# 03.net
KiCad netlist of a schematic drawn in Altium Designer
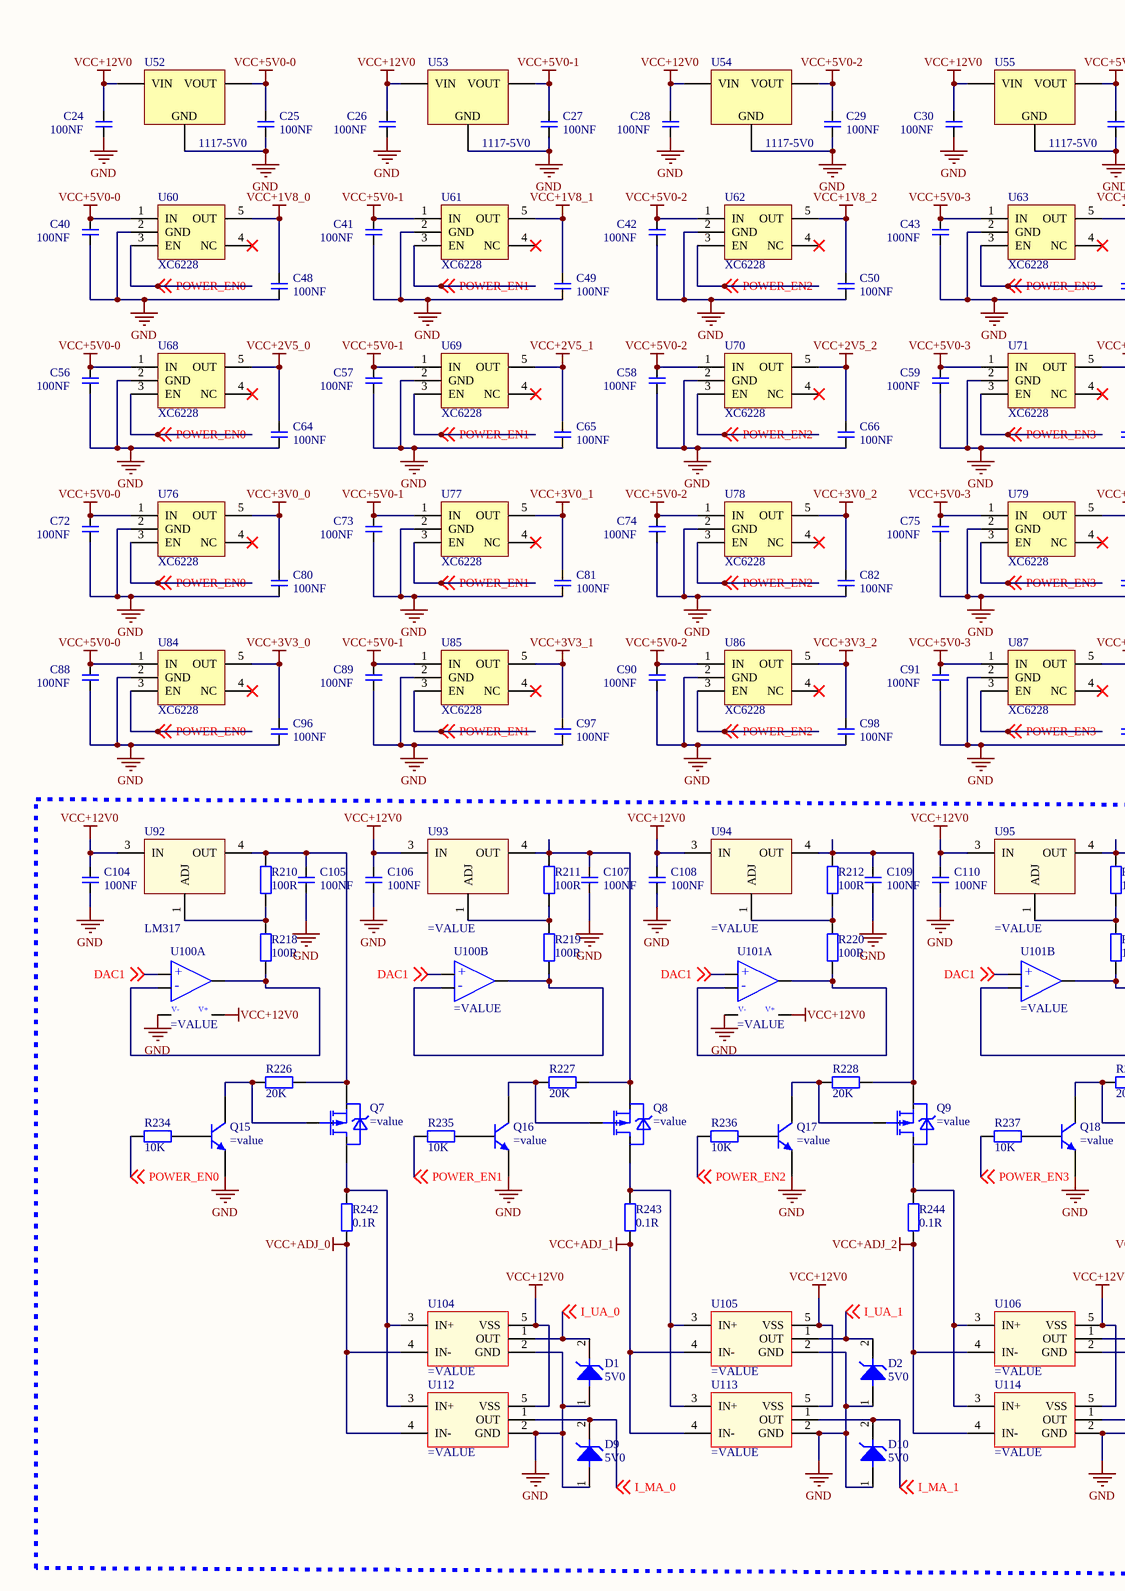
[diagram p0: 通用工装板03.SchDoc, left]
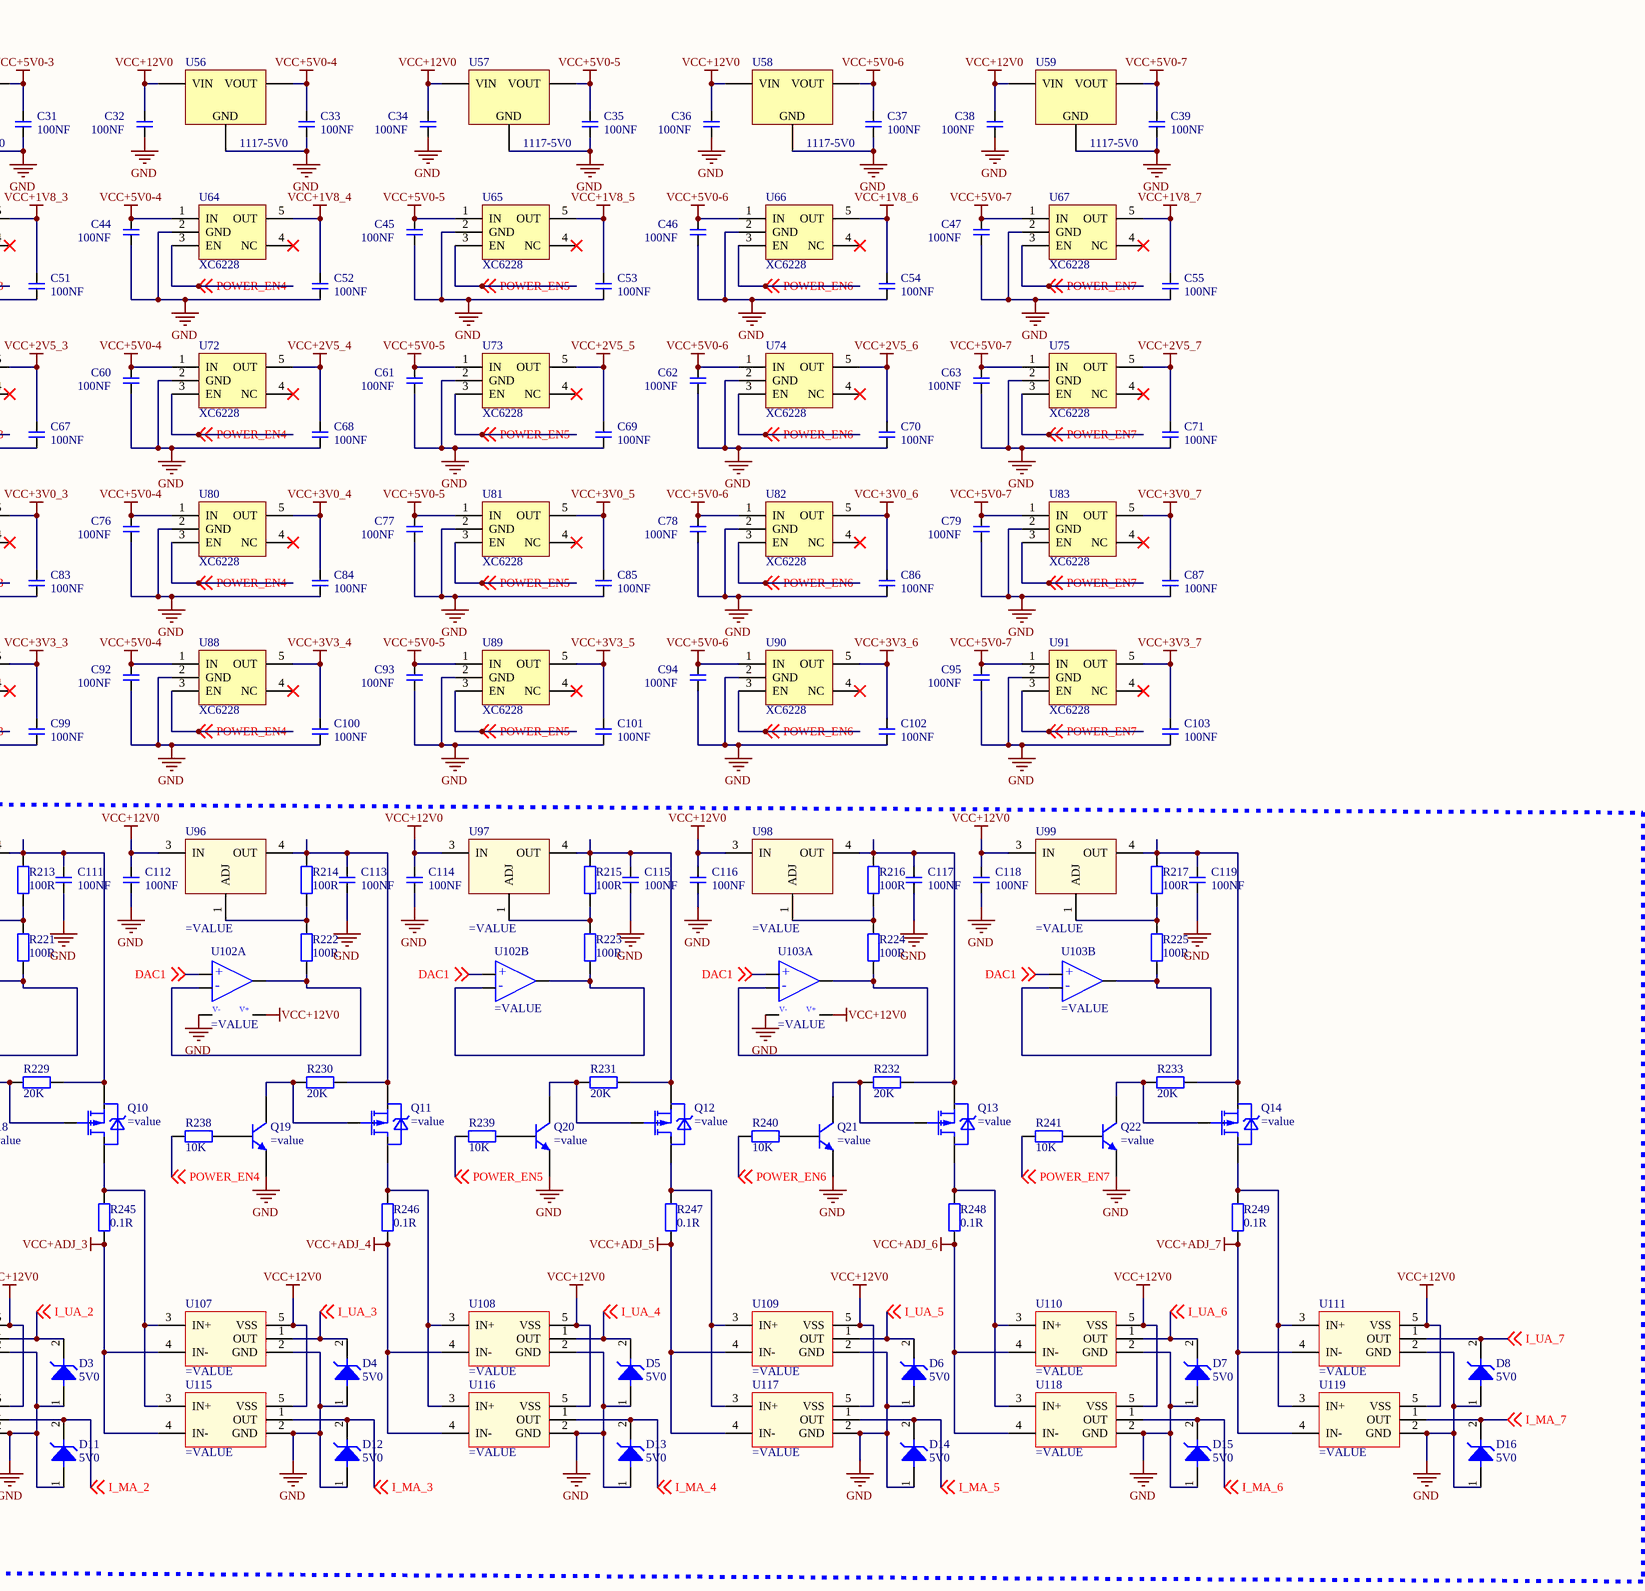
[diagram p1: 通用工装板03.SchDoc, right]

(export (version "E")
  (design (tool "Eeschema 10.0.6"))
  (components
    (comp (ref "C24")
      (value "100NF")
      (footprint "c0402")
      (description "无极性电容")
      (libsource (lib "瑞臻信息") (part "无极性电容"))
    )
    (comp (ref "C25")
      (value "100NF")
      (footprint "c0402")
      (description "无极性电容")
      (libsource (lib "瑞臻信息") (part "无极性电容"))
    )
    (comp (ref "C26")
      (value "100NF")
      (footprint "c0402")
      (description "无极性电容")
      (libsource (lib "瑞臻信息") (part "无极性电容"))
    )
    (comp (ref "C27")
      (value "100NF")
      (footprint "c0402")
      (description "无极性电容")
      (libsource (lib "瑞臻信息") (part "无极性电容"))
    )
    (comp (ref "C28")
      (value "100NF")
      (footprint "c0402")
      (description "无极性电容")
      (libsource (lib "瑞臻信息") (part "无极性电容"))
    )
    (comp (ref "C29")
      (value "100NF")
      (footprint "c0402")
      (description "无极性电容")
      (libsource (lib "瑞臻信息") (part "无极性电容"))
    )
    (comp (ref "C30")
      (value "100NF")
      (footprint "c0402")
      (description "无极性电容")
      (libsource (lib "瑞臻信息") (part "无极性电容"))
    )
    (comp (ref "C31")
      (value "100NF")
      (footprint "c0402")
      (description "无极性电容")
      (libsource (lib "瑞臻信息") (part "无极性电容"))
    )
    (comp (ref "C32")
      (value "100NF")
      (footprint "c0402")
      (description "无极性电容")
      (libsource (lib "瑞臻信息") (part "无极性电容"))
    )
    (comp (ref "C33")
      (value "100NF")
      (footprint "c0402")
      (description "无极性电容")
      (libsource (lib "瑞臻信息") (part "无极性电容"))
    )
    (comp (ref "C34")
      (value "100NF")
      (footprint "c0402")
      (description "无极性电容")
      (libsource (lib "瑞臻信息") (part "无极性电容"))
    )
    (comp (ref "C35")
      (value "100NF")
      (footprint "c0402")
      (description "无极性电容")
      (libsource (lib "瑞臻信息") (part "无极性电容"))
    )
    (comp (ref "C36")
      (value "100NF")
      (footprint "c0402")
      (description "无极性电容")
      (libsource (lib "瑞臻信息") (part "无极性电容"))
    )
    (comp (ref "C37")
      (value "100NF")
      (footprint "c0402")
      (description "无极性电容")
      (libsource (lib "瑞臻信息") (part "无极性电容"))
    )
    (comp (ref "C38")
      (value "100NF")
      (footprint "c0402")
      (description "无极性电容")
      (libsource (lib "瑞臻信息") (part "无极性电容"))
    )
    (comp (ref "C39")
      (value "100NF")
      (footprint "c0402")
      (description "无极性电容")
      (libsource (lib "瑞臻信息") (part "无极性电容"))
    )
    (comp (ref "C40")
      (value "100NF")
      (footprint "c0402")
      (description "无极性电容")
      (libsource (lib "瑞臻信息") (part "无极性电容"))
    )
    (comp (ref "C41")
      (value "100NF")
      (footprint "c0402")
      (description "无极性电容")
      (libsource (lib "瑞臻信息") (part "无极性电容"))
    )
    (comp (ref "C42")
      (value "100NF")
      (footprint "c0402")
      (description "无极性电容")
      (libsource (lib "瑞臻信息") (part "无极性电容"))
    )
    (comp (ref "C43")
      (value "100NF")
      (footprint "c0402")
      (description "无极性电容")
      (libsource (lib "瑞臻信息") (part "无极性电容"))
    )
    (comp (ref "C44")
      (value "100NF")
      (footprint "c0402")
      (description "无极性电容")
      (libsource (lib "瑞臻信息") (part "无极性电容"))
    )
    (comp (ref "C45")
      (value "100NF")
      (footprint "c0402")
      (description "无极性电容")
      (libsource (lib "瑞臻信息") (part "无极性电容"))
    )
    (comp (ref "C46")
      (value "100NF")
      (footprint "c0402")
      (description "无极性电容")
      (libsource (lib "瑞臻信息") (part "无极性电容"))
    )
    (comp (ref "C47")
      (value "100NF")
      (footprint "c0402")
      (description "无极性电容")
      (libsource (lib "瑞臻信息") (part "无极性电容"))
    )
    (comp (ref "C48")
      (value "100NF")
      (footprint "c0402")
      (description "无极性电容")
      (libsource (lib "瑞臻信息") (part "无极性电容"))
    )
    (comp (ref "C49")
      (value "100NF")
      (footprint "c0402")
      (description "无极性电容")
      (libsource (lib "瑞臻信息") (part "无极性电容"))
    )
    (comp (ref "C50")
      (value "100NF")
      (footprint "c0402")
      (description "无极性电容")
      (libsource (lib "瑞臻信息") (part "无极性电容"))
    )
    (comp (ref "C51")
      (value "100NF")
      (footprint "c0402")
      (description "无极性电容")
      (libsource (lib "瑞臻信息") (part "无极性电容"))
    )
    (comp (ref "C52")
      (value "100NF")
      (footprint "c0402")
      (description "无极性电容")
      (libsource (lib "瑞臻信息") (part "无极性电容"))
    )
    (comp (ref "C53")
      (value "100NF")
      (footprint "c0402")
      (description "无极性电容")
      (libsource (lib "瑞臻信息") (part "无极性电容"))
    )
    (comp (ref "C54")
      (value "100NF")
      (footprint "c0402")
      (description "无极性电容")
      (libsource (lib "瑞臻信息") (part "无极性电容"))
    )
    (comp (ref "C55")
      (value "100NF")
      (footprint "c0402")
      (description "无极性电容")
      (libsource (lib "瑞臻信息") (part "无极性电容"))
    )
    (comp (ref "C56")
      (value "100NF")
      (footprint "c0402")
      (description "无极性电容")
      (libsource (lib "瑞臻信息") (part "无极性电容"))
    )
    (comp (ref "C57")
      (value "100NF")
      (footprint "c0402")
      (description "无极性电容")
      (libsource (lib "瑞臻信息") (part "无极性电容"))
    )
    (comp (ref "C58")
      (value "100NF")
      (footprint "c0402")
      (description "无极性电容")
      (libsource (lib "瑞臻信息") (part "无极性电容"))
    )
    (comp (ref "C59")
      (value "100NF")
      (footprint "c0402")
      (description "无极性电容")
      (libsource (lib "瑞臻信息") (part "无极性电容"))
    )
    (comp (ref "C60")
      (value "100NF")
      (footprint "c0402")
      (description "无极性电容")
      (libsource (lib "瑞臻信息") (part "无极性电容"))
    )
    (comp (ref "C61")
      (value "100NF")
      (footprint "c0402")
      (description "无极性电容")
      (libsource (lib "瑞臻信息") (part "无极性电容"))
    )
    (comp (ref "C62")
      (value "100NF")
      (footprint "c0402")
      (description "无极性电容")
      (libsource (lib "瑞臻信息") (part "无极性电容"))
    )
    (comp (ref "C63")
      (value "100NF")
      (footprint "c0402")
      (description "无极性电容")
      (libsource (lib "瑞臻信息") (part "无极性电容"))
    )
    (comp (ref "C64")
      (value "100NF")
      (footprint "c0402")
      (description "无极性电容")
      (libsource (lib "瑞臻信息") (part "无极性电容"))
    )
    (comp (ref "C65")
      (value "100NF")
      (footprint "c0402")
      (description "无极性电容")
      (libsource (lib "瑞臻信息") (part "无极性电容"))
    )
    (comp (ref "C66")
      (value "100NF")
      (footprint "c0402")
      (description "无极性电容")
      (libsource (lib "瑞臻信息") (part "无极性电容"))
    )
    (comp (ref "C67")
      (value "100NF")
      (footprint "c0402")
      (description "无极性电容")
      (libsource (lib "瑞臻信息") (part "无极性电容"))
    )
    (comp (ref "C68")
      (value "100NF")
      (footprint "c0402")
      (description "无极性电容")
      (libsource (lib "瑞臻信息") (part "无极性电容"))
    )
    (comp (ref "C69")
      (value "100NF")
      (footprint "c0402")
      (description "无极性电容")
      (libsource (lib "瑞臻信息") (part "无极性电容"))
    )
    (comp (ref "C70")
      (value "100NF")
      (footprint "c0402")
      (description "无极性电容")
      (libsource (lib "瑞臻信息") (part "无极性电容"))
    )
    (comp (ref "C71")
      (value "100NF")
      (footprint "c0402")
      (description "无极性电容")
      (libsource (lib "瑞臻信息") (part "无极性电容"))
    )
    (comp (ref "C72")
      (value "100NF")
      (footprint "c0402")
      (description "无极性电容")
      (libsource (lib "瑞臻信息") (part "无极性电容"))
    )
    (comp (ref "C73")
      (value "100NF")
      (footprint "c0402")
      (description "无极性电容")
      (libsource (lib "瑞臻信息") (part "无极性电容"))
    )
    (comp (ref "C74")
      (value "100NF")
      (footprint "c0402")
      (description "无极性电容")
      (libsource (lib "瑞臻信息") (part "无极性电容"))
    )
    (comp (ref "C75")
      (value "100NF")
      (footprint "c0402")
      (description "无极性电容")
      (libsource (lib "瑞臻信息") (part "无极性电容"))
    )
    (comp (ref "C76")
      (value "100NF")
      (footprint "c0402")
      (description "无极性电容")
      (libsource (lib "瑞臻信息") (part "无极性电容"))
    )
    (comp (ref "C77")
      (value "100NF")
      (footprint "c0402")
      (description "无极性电容")
      (libsource (lib "瑞臻信息") (part "无极性电容"))
    )
    (comp (ref "C78")
      (value "100NF")
      (footprint "c0402")
      (description "无极性电容")
      (libsource (lib "瑞臻信息") (part "无极性电容"))
    )
    (comp (ref "C79")
      (value "100NF")
      (footprint "c0402")
      (description "无极性电容")
      (libsource (lib "瑞臻信息") (part "无极性电容"))
    )
    (comp (ref "C80")
      (value "100NF")
      (footprint "c0402")
      (description "无极性电容")
      (libsource (lib "瑞臻信息") (part "无极性电容"))
    )
    (comp (ref "C81")
      (value "100NF")
      (footprint "c0402")
      (description "无极性电容")
      (libsource (lib "瑞臻信息") (part "无极性电容"))
    )
    (comp (ref "C82")
      (value "100NF")
      (footprint "c0402")
      (description "无极性电容")
      (libsource (lib "瑞臻信息") (part "无极性电容"))
    )
    (comp (ref "C83")
      (value "100NF")
      (footprint "c0402")
      (description "无极性电容")
      (libsource (lib "瑞臻信息") (part "无极性电容"))
    )
    (comp (ref "C84")
      (value "100NF")
      (footprint "c0402")
      (description "无极性电容")
      (libsource (lib "瑞臻信息") (part "无极性电容"))
    )
    (comp (ref "C85")
      (value "100NF")
      (footprint "c0402")
      (description "无极性电容")
      (libsource (lib "瑞臻信息") (part "无极性电容"))
    )
    (comp (ref "C86")
      (value "100NF")
      (footprint "c0402")
      (description "无极性电容")
      (libsource (lib "瑞臻信息") (part "无极性电容"))
    )
    (comp (ref "C87")
      (value "100NF")
      (footprint "c0402")
      (description "无极性电容")
      (libsource (lib "瑞臻信息") (part "无极性电容"))
    )
    (comp (ref "C88")
      (value "100NF")
      (footprint "c0402")
      (description "无极性电容")
      (libsource (lib "瑞臻信息") (part "无极性电容"))
    )
    (comp (ref "C89")
      (value "100NF")
      (footprint "c0402")
      (description "无极性电容")
      (libsource (lib "瑞臻信息") (part "无极性电容"))
    )
    (comp (ref "C90")
      (value "100NF")
      (footprint "c0402")
      (description "无极性电容")
      (libsource (lib "瑞臻信息") (part "无极性电容"))
    )
    (comp (ref "C91")
      (value "100NF")
      (footprint "c0402")
      (description "无极性电容")
      (libsource (lib "瑞臻信息") (part "无极性电容"))
    )
    (comp (ref "C92")
      (value "100NF")
      (footprint "c0402")
      (description "无极性电容")
      (libsource (lib "瑞臻信息") (part "无极性电容"))
    )
    (comp (ref "C93")
      (value "100NF")
      (footprint "c0402")
      (description "无极性电容")
      (libsource (lib "瑞臻信息") (part "无极性电容"))
    )
    (comp (ref "C94")
      (value "100NF")
      (footprint "c0402")
      (description "无极性电容")
      (libsource (lib "瑞臻信息") (part "无极性电容"))
    )
    (comp (ref "C95")
      (value "100NF")
      (footprint "c0402")
      (description "无极性电容")
      (libsource (lib "瑞臻信息") (part "无极性电容"))
    )
    (comp (ref "C96")
      (value "100NF")
      (footprint "c0402")
      (description "无极性电容")
      (libsource (lib "瑞臻信息") (part "无极性电容"))
    )
    (comp (ref "C97")
      (value "100NF")
      (footprint "c0402")
      (description "无极性电容")
      (libsource (lib "瑞臻信息") (part "无极性电容"))
    )
    (comp (ref "C98")
      (value "100NF")
      (footprint "c0402")
      (description "无极性电容")
      (libsource (lib "瑞臻信息") (part "无极性电容"))
    )
    (comp (ref "C99")
      (value "100NF")
      (footprint "c0402")
      (description "无极性电容")
      (libsource (lib "瑞臻信息") (part "无极性电容"))
    )
    (comp (ref "C100")
      (value "100NF")
      (footprint "c0402")
      (description "无极性电容")
      (libsource (lib "瑞臻信息") (part "无极性电容"))
    )
    (comp (ref "C101")
      (value "100NF")
      (footprint "c0402")
      (description "无极性电容")
      (libsource (lib "瑞臻信息") (part "无极性电容"))
    )
    (comp (ref "C102")
      (value "100NF")
      (footprint "c0402")
      (description "无极性电容")
      (libsource (lib "瑞臻信息") (part "无极性电容"))
    )
    (comp (ref "C103")
      (value "100NF")
      (footprint "c0402")
      (description "无极性电容")
      (libsource (lib "瑞臻信息") (part "无极性电容"))
    )
    (comp (ref "C104")
      (value "100NF")
      (footprint "c0402")
      (description "无极性电容")
      (libsource (lib "瑞臻信息") (part "无极性电容"))
    )
    (comp (ref "C105")
      (value "100NF")
      (footprint "c0402")
      (description "无极性电容")
      (libsource (lib "瑞臻信息") (part "无极性电容"))
    )
    (comp (ref "C106")
      (value "100NF")
      (footprint "c0402")
      (description "无极性电容")
      (libsource (lib "瑞臻信息") (part "无极性电容"))
    )
    (comp (ref "C107")
      (value "100NF")
      (footprint "c0402")
      (description "无极性电容")
      (libsource (lib "瑞臻信息") (part "无极性电容"))
    )
    (comp (ref "C108")
      (value "100NF")
      (footprint "c0402")
      (description "无极性电容")
      (libsource (lib "瑞臻信息") (part "无极性电容"))
    )
    (comp (ref "C109")
      (value "100NF")
      (footprint "c0402")
      (description "无极性电容")
      (libsource (lib "瑞臻信息") (part "无极性电容"))
    )
    (comp (ref "C110")
      (value "100NF")
      (footprint "c0402")
      (description "无极性电容")
      (libsource (lib "瑞臻信息") (part "无极性电容"))
    )
    (comp (ref "C111")
      (value "100NF")
      (footprint "c0402")
      (description "无极性电容")
      (libsource (lib "瑞臻信息") (part "无极性电容"))
    )
    (comp (ref "C112")
      (value "100NF")
      (footprint "c0402")
      (description "无极性电容")
      (libsource (lib "瑞臻信息") (part "无极性电容"))
    )
    (comp (ref "C113")
      (value "100NF")
      (footprint "c0402")
      (description "无极性电容")
      (libsource (lib "瑞臻信息") (part "无极性电容"))
    )
    (comp (ref "C114")
      (value "100NF")
      (footprint "c0402")
      (description "无极性电容")
      (libsource (lib "瑞臻信息") (part "无极性电容"))
    )
    (comp (ref "C115")
      (value "100NF")
      (footprint "c0402")
      (description "无极性电容")
      (libsource (lib "瑞臻信息") (part "无极性电容"))
    )
    (comp (ref "C116")
      (value "100NF")
      (footprint "c0402")
      (description "无极性电容")
      (libsource (lib "瑞臻信息") (part "无极性电容"))
    )
    (comp (ref "C117")
      (value "100NF")
      (footprint "c0402")
      (description "无极性电容")
      (libsource (lib "瑞臻信息") (part "无极性电容"))
    )
    (comp (ref "C118")
      (value "100NF")
      (footprint "c0402")
      (description "无极性电容")
      (libsource (lib "瑞臻信息") (part "无极性电容"))
    )
    (comp (ref "C119")
      (value "100NF")
      (footprint "c0402")
      (description "无极性电容")
      (libsource (lib "瑞臻信息") (part "无极性电容"))
    )
    (comp (ref "D1")
      (value "5V0")
      (footprint "LL34_2P_D1R5H3R7")
      (description "齐纳二极管")
      (libsource (lib "瑞臻信息") (part "齐纳二极管"))
    )
    (comp (ref "D2")
      (value "5V0")
      (footprint "LL34_2P_D1R5H3R7")
      (description "齐纳二极管")
      (libsource (lib "瑞臻信息") (part "齐纳二极管"))
    )
    (comp (ref "D3")
      (value "5V0")
      (footprint "LL34_2P_D1R5H3R7")
      (description "齐纳二极管")
      (libsource (lib "瑞臻信息") (part "齐纳二极管"))
    )
    (comp (ref "D4")
      (value "5V0")
      (footprint "LL34_2P_D1R5H3R7")
      (description "齐纳二极管")
      (libsource (lib "瑞臻信息") (part "齐纳二极管"))
    )
    (comp (ref "D5")
      (value "5V0")
      (footprint "LL34_2P_D1R5H3R7")
      (description "齐纳二极管")
      (libsource (lib "瑞臻信息") (part "齐纳二极管"))
    )
    (comp (ref "D6")
      (value "5V0")
      (footprint "LL34_2P_D1R5H3R7")
      (description "齐纳二极管")
      (libsource (lib "瑞臻信息") (part "齐纳二极管"))
    )
    (comp (ref "D7")
      (value "5V0")
      (footprint "LL34_2P_D1R5H3R7")
      (description "齐纳二极管")
      (libsource (lib "瑞臻信息") (part "齐纳二极管"))
    )
    (comp (ref "D8")
      (value "5V0")
      (footprint "LL34_2P_D1R5H3R7")
      (description "齐纳二极管")
      (libsource (lib "瑞臻信息") (part "齐纳二极管"))
    )
    (comp (ref "D9")
      (value "5V0")
      (footprint "LL34_2P_D1R5H3R7")
      (description "齐纳二极管")
      (libsource (lib "瑞臻信息") (part "齐纳二极管"))
    )
    (comp (ref "D10")
      (value "5V0")
      (footprint "LL34_2P_D1R5H3R7")
      (description "齐纳二极管")
      (libsource (lib "瑞臻信息") (part "齐纳二极管"))
    )
    (comp (ref "D11")
      (value "5V0")
      (footprint "LL34_2P_D1R5H3R7")
      (description "齐纳二极管")
      (libsource (lib "瑞臻信息") (part "齐纳二极管"))
    )
    (comp (ref "D12")
      (value "5V0")
      (footprint "LL34_2P_D1R5H3R7")
      (description "齐纳二极管")
      (libsource (lib "瑞臻信息") (part "齐纳二极管"))
    )
    (comp (ref "D13")
      (value "5V0")
      (footprint "LL34_2P_D1R5H3R7")
      (description "齐纳二极管")
      (libsource (lib "瑞臻信息") (part "齐纳二极管"))
    )
    (comp (ref "D14")
      (value "5V0")
      (footprint "LL34_2P_D1R5H3R7")
      (description "齐纳二极管")
      (libsource (lib "瑞臻信息") (part "齐纳二极管"))
    )
    (comp (ref "D15")
      (value "5V0")
      (footprint "LL34_2P_D1R5H3R7")
      (description "齐纳二极管")
      (libsource (lib "瑞臻信息") (part "齐纳二极管"))
    )
    (comp (ref "D16")
      (value "5V0")
      (footprint "LL34_2P_D1R5H3R7")
      (description "齐纳二极管")
      (libsource (lib "瑞臻信息") (part "齐纳二极管"))
    )
    (comp (ref "Q7")
      (value "~")
      (footprint "SOT23_3P_0R95_1R3X2R9")
      (description "P-MOS")
      (libsource (lib "瑞臻信息") (part "P-MOS"))
    )
    (comp (ref "Q8")
      (value "~")
      (footprint "SOT23_3P_0R95_1R3X2R9")
      (description "P-MOS")
      (libsource (lib "瑞臻信息") (part "P-MOS"))
    )
    (comp (ref "Q9")
      (value "~")
      (footprint "SOT23_3P_0R95_1R3X2R9")
      (description "P-MOS")
      (libsource (lib "瑞臻信息") (part "P-MOS"))
    )
    (comp (ref "Q10")
      (value "~")
      (footprint "SOT23_3P_0R95_1R3X2R9")
      (description "P-MOS")
      (libsource (lib "瑞臻信息") (part "P-MOS"))
    )
    (comp (ref "Q11")
      (value "~")
      (footprint "SOT23_3P_0R95_1R3X2R9")
      (description "P-MOS")
      (libsource (lib "瑞臻信息") (part "P-MOS"))
    )
    (comp (ref "Q12")
      (value "~")
      (footprint "SOT23_3P_0R95_1R3X2R9")
      (description "P-MOS")
      (libsource (lib "瑞臻信息") (part "P-MOS"))
    )
    (comp (ref "Q13")
      (value "~")
      (footprint "SOT23_3P_0R95_1R3X2R9")
      (description "P-MOS")
      (libsource (lib "瑞臻信息") (part "P-MOS"))
    )
    (comp (ref "Q14")
      (value "~")
      (footprint "SOT23_3P_0R95_1R3X2R9")
      (description "P-MOS")
      (libsource (lib "瑞臻信息") (part "P-MOS"))
    )
    (comp (ref "Q15")
      (value "~")
      (footprint "SOT23_3P_0R95_1R3X2R9")
      (description "NPN三极管")
      (libsource (lib "瑞臻信息") (part "NPN三极管"))
    )
    (comp (ref "Q16")
      (value "~")
      (footprint "SOT23_3P_0R95_1R3X2R9")
      (description "NPN三极管")
      (libsource (lib "瑞臻信息") (part "NPN三极管"))
    )
    (comp (ref "Q17")
      (value "~")
      (footprint "SOT23_3P_0R95_1R3X2R9")
      (description "NPN三极管")
      (libsource (lib "瑞臻信息") (part "NPN三极管"))
    )
    (comp (ref "Q18")
      (value "~")
      (footprint "SOT23_3P_0R95_1R3X2R9")
      (description "NPN三极管")
      (libsource (lib "瑞臻信息") (part "NPN三极管"))
    )
    (comp (ref "Q19")
      (value "~")
      (footprint "SOT23_3P_0R95_1R3X2R9")
      (description "NPN三极管")
      (libsource (lib "瑞臻信息") (part "NPN三极管"))
    )
    (comp (ref "Q20")
      (value "~")
      (footprint "SOT23_3P_0R95_1R3X2R9")
      (description "NPN三极管")
      (libsource (lib "瑞臻信息") (part "NPN三极管"))
    )
    (comp (ref "Q21")
      (value "~")
      (footprint "SOT23_3P_0R95_1R3X2R9")
      (description "NPN三极管")
      (libsource (lib "瑞臻信息") (part "NPN三极管"))
    )
    (comp (ref "Q22")
      (value "~")
      (footprint "SOT23_3P_0R95_1R3X2R9")
      (description "NPN三极管")
      (libsource (lib "瑞臻信息") (part "NPN三极管"))
    )
    (comp (ref "R210")
      (value "100R")
      (footprint "r0402")
      (description "普通电阻")
      (libsource (lib "") (part "普通电阻_1"))
    )
    (comp (ref "R211")
      (value "100R")
      (footprint "r0402")
      (description "普通电阻")
      (libsource (lib "") (part "普通电阻_1"))
    )
    (comp (ref "R212")
      (value "100R")
      (footprint "r0402")
      (description "普通电阻")
      (libsource (lib "") (part "普通电阻_1"))
    )
    (comp (ref "R213")
      (value "100R")
      (footprint "r0402")
      (description "普通电阻")
      (libsource (lib "") (part "普通电阻_1"))
    )
    (comp (ref "R214")
      (value "100R")
      (footprint "r0402")
      (description "普通电阻")
      (libsource (lib "") (part "普通电阻_1"))
    )
    (comp (ref "R215")
      (value "100R")
      (footprint "r0402")
      (description "普通电阻")
      (libsource (lib "") (part "普通电阻_1"))
    )
    (comp (ref "R216")
      (value "100R")
      (footprint "r0402")
      (description "普通电阻")
      (libsource (lib "") (part "普通电阻_1"))
    )
    (comp (ref "R217")
      (value "100R")
      (footprint "r0402")
      (description "普通电阻")
      (libsource (lib "") (part "普通电阻_1"))
    )
    (comp (ref "R218")
      (value "100R")
      (footprint "r0402")
      (description "普通电阻")
      (libsource (lib "") (part "普通电阻_1"))
    )
    (comp (ref "R219")
      (value "100R")
      (footprint "r0402")
      (description "普通电阻")
      (libsource (lib "") (part "普通电阻_1"))
    )
    (comp (ref "R220")
      (value "100R")
      (footprint "r0402")
      (description "普通电阻")
      (libsource (lib "") (part "普通电阻_1"))
    )
    (comp (ref "R221")
      (value "100R")
      (footprint "r0402")
      (description "普通电阻")
      (libsource (lib "") (part "普通电阻_1"))
    )
    (comp (ref "R222")
      (value "100R")
      (footprint "r0402")
      (description "普通电阻")
      (libsource (lib "") (part "普通电阻_1"))
    )
    (comp (ref "R223")
      (value "100R")
      (footprint "r0402")
      (description "普通电阻")
      (libsource (lib "") (part "普通电阻_1"))
    )
    (comp (ref "R224")
      (value "100R")
      (footprint "r0402")
      (description "普通电阻")
      (libsource (lib "") (part "普通电阻_1"))
    )
    (comp (ref "R225")
      (value "100R")
      (footprint "r0402")
      (description "普通电阻")
      (libsource (lib "") (part "普通电阻_1"))
    )
    (comp (ref "R226")
      (value "20K")
      (footprint "r0402")
      (description "普通电阻")
      (libsource (lib "瑞臻信息") (part "普通电阻"))
    )
    (comp (ref "R227")
      (value "20K")
      (footprint "r0402")
      (description "普通电阻")
      (libsource (lib "瑞臻信息") (part "普通电阻"))
    )
    (comp (ref "R228")
      (value "20K")
      (footprint "r0402")
      (description "普通电阻")
      (libsource (lib "瑞臻信息") (part "普通电阻"))
    )
    (comp (ref "R229")
      (value "20K")
      (footprint "r0402")
      (description "普通电阻")
      (libsource (lib "瑞臻信息") (part "普通电阻"))
    )
    (comp (ref "R230")
      (value "20K")
      (footprint "r0402")
      (description "普通电阻")
      (libsource (lib "瑞臻信息") (part "普通电阻"))
    )
    (comp (ref "R231")
      (value "20K")
      (footprint "r0402")
      (description "普通电阻")
      (libsource (lib "瑞臻信息") (part "普通电阻"))
    )
    (comp (ref "R232")
      (value "20K")
      (footprint "r0402")
      (description "普通电阻")
      (libsource (lib "瑞臻信息") (part "普通电阻"))
    )
    (comp (ref "R233")
      (value "20K")
      (footprint "r0402")
      (description "普通电阻")
      (libsource (lib "瑞臻信息") (part "普通电阻"))
    )
    (comp (ref "R234")
      (value "10K")
      (footprint "r0402")
      (description "普通电阻")
      (libsource (lib "瑞臻信息") (part "普通电阻"))
    )
    (comp (ref "R235")
      (value "10K")
      (footprint "r0402")
      (description "普通电阻")
      (libsource (lib "瑞臻信息") (part "普通电阻"))
    )
    (comp (ref "R236")
      (value "10K")
      (footprint "r0402")
      (description "普通电阻")
      (libsource (lib "瑞臻信息") (part "普通电阻"))
    )
    (comp (ref "R237")
      (value "10K")
      (footprint "r0402")
      (description "普通电阻")
      (libsource (lib "瑞臻信息") (part "普通电阻"))
    )
    (comp (ref "R238")
      (value "10K")
      (footprint "r0402")
      (description "普通电阻")
      (libsource (lib "瑞臻信息") (part "普通电阻"))
    )
    (comp (ref "R239")
      (value "10K")
      (footprint "r0402")
      (description "普通电阻")
      (libsource (lib "瑞臻信息") (part "普通电阻"))
    )
    (comp (ref "R240")
      (value "10K")
      (footprint "r0402")
      (description "普通电阻")
      (libsource (lib "瑞臻信息") (part "普通电阻"))
    )
    (comp (ref "R241")
      (value "10K")
      (footprint "r0402")
      (description "普通电阻")
      (libsource (lib "瑞臻信息") (part "普通电阻"))
    )
    (comp (ref "R242")
      (value "0.1R")
      (footprint "r0603")
      (description "普通电阻")
      (libsource (lib "") (part "普通电阻_2"))
    )
    (comp (ref "R243")
      (value "0.1R")
      (footprint "r0603")
      (description "普通电阻")
      (libsource (lib "") (part "普通电阻_2"))
    )
    (comp (ref "R244")
      (value "0.1R")
      (footprint "r0603")
      (description "普通电阻")
      (libsource (lib "") (part "普通电阻_2"))
    )
    (comp (ref "R245")
      (value "0.1R")
      (footprint "r0603")
      (description "普通电阻")
      (libsource (lib "") (part "普通电阻_2"))
    )
    (comp (ref "R246")
      (value "0.1R")
      (footprint "r0603")
      (description "普通电阻")
      (libsource (lib "") (part "普通电阻_2"))
    )
    (comp (ref "R247")
      (value "0.1R")
      (footprint "r0603")
      (description "普通电阻")
      (libsource (lib "") (part "普通电阻_2"))
    )
    (comp (ref "R248")
      (value "0.1R")
      (footprint "r0603")
      (description "普通电阻")
      (libsource (lib "") (part "普通电阻_2"))
    )
    (comp (ref "R249")
      (value "0.1R")
      (footprint "r0603")
      (description "普通电阻")
      (libsource (lib "") (part "普通电阻_2"))
    )
    (comp (ref "U52")
      (value "1117-5V0")
      (footprint "SOT223_4P_2R3_3R7X6R7")
      (libsource (lib "瑞臻信息") (part "AMS1117"))
    )
    (comp (ref "U53")
      (value "1117-5V0")
      (footprint "SOT223_4P_2R3_3R7X6R7")
      (libsource (lib "瑞臻信息") (part "AMS1117"))
    )
    (comp (ref "U54")
      (value "1117-5V0")
      (footprint "SOT223_4P_2R3_3R7X6R7")
      (libsource (lib "瑞臻信息") (part "AMS1117"))
    )
    (comp (ref "U55")
      (value "1117-5V0")
      (footprint "SOT223_4P_2R3_3R7X6R7")
      (libsource (lib "瑞臻信息") (part "AMS1117"))
    )
    (comp (ref "U56")
      (value "1117-5V0")
      (footprint "SOT223_4P_2R3_3R7X6R7")
      (libsource (lib "瑞臻信息") (part "AMS1117"))
    )
    (comp (ref "U57")
      (value "1117-5V0")
      (footprint "SOT223_4P_2R3_3R7X6R7")
      (libsource (lib "瑞臻信息") (part "AMS1117"))
    )
    (comp (ref "U58")
      (value "1117-5V0")
      (footprint "SOT223_4P_2R3_3R7X6R7")
      (libsource (lib "瑞臻信息") (part "AMS1117"))
    )
    (comp (ref "U59")
      (value "1117-5V0")
      (footprint "SOT223_4P_2R3_3R7X6R7")
      (libsource (lib "瑞臻信息") (part "AMS1117"))
    )
    (comp (ref "U60")
      (value "XC6228")
      (footprint "SOT23_5P_0R95_1R6X2R9")
      (libsource (lib "瑞臻信息") (part "XC6228"))
    )
    (comp (ref "U61")
      (value "XC6228")
      (footprint "SOT23_5P_0R95_1R6X2R9")
      (libsource (lib "瑞臻信息") (part "XC6228"))
    )
    (comp (ref "U62")
      (value "XC6228")
      (footprint "SOT23_5P_0R95_1R6X2R9")
      (libsource (lib "瑞臻信息") (part "XC6228"))
    )
    (comp (ref "U63")
      (value "XC6228")
      (footprint "SOT23_5P_0R95_1R6X2R9")
      (libsource (lib "瑞臻信息") (part "XC6228"))
    )
    (comp (ref "U64")
      (value "XC6228")
      (footprint "SOT23_5P_0R95_1R6X2R9")
      (libsource (lib "瑞臻信息") (part "XC6228"))
    )
    (comp (ref "U65")
      (value "XC6228")
      (footprint "SOT23_5P_0R95_1R6X2R9")
      (libsource (lib "瑞臻信息") (part "XC6228"))
    )
    (comp (ref "U66")
      (value "XC6228")
      (footprint "SOT23_5P_0R95_1R6X2R9")
      (libsource (lib "瑞臻信息") (part "XC6228"))
    )
    (comp (ref "U67")
      (value "XC6228")
      (footprint "SOT23_5P_0R95_1R6X2R9")
      (libsource (lib "瑞臻信息") (part "XC6228"))
    )
    (comp (ref "U68")
      (value "XC6228")
      (footprint "SOT23_5P_0R95_1R6X2R9")
      (libsource (lib "瑞臻信息") (part "XC6228"))
    )
    (comp (ref "U69")
      (value "XC6228")
      (footprint "SOT23_5P_0R95_1R6X2R9")
      (libsource (lib "瑞臻信息") (part "XC6228"))
    )
    (comp (ref "U70")
      (value "XC6228")
      (footprint "SOT23_5P_0R95_1R6X2R9")
      (libsource (lib "瑞臻信息") (part "XC6228"))
    )
    (comp (ref "U71")
      (value "XC6228")
      (footprint "SOT23_5P_0R95_1R6X2R9")
      (libsource (lib "瑞臻信息") (part "XC6228"))
    )
    (comp (ref "U72")
      (value "XC6228")
      (footprint "SOT23_5P_0R95_1R6X2R9")
      (libsource (lib "瑞臻信息") (part "XC6228"))
    )
    (comp (ref "U73")
      (value "XC6228")
      (footprint "SOT23_5P_0R95_1R6X2R9")
      (libsource (lib "瑞臻信息") (part "XC6228"))
    )
    (comp (ref "U74")
      (value "XC6228")
      (footprint "SOT23_5P_0R95_1R6X2R9")
      (libsource (lib "瑞臻信息") (part "XC6228"))
    )
    (comp (ref "U75")
      (value "XC6228")
      (footprint "SOT23_5P_0R95_1R6X2R9")
      (libsource (lib "瑞臻信息") (part "XC6228"))
    )
    (comp (ref "U76")
      (value "XC6228")
      (footprint "SOT23_5P_0R95_1R6X2R9")
      (libsource (lib "瑞臻信息") (part "XC6228"))
    )
    (comp (ref "U77")
      (value "XC6228")
      (footprint "SOT23_5P_0R95_1R6X2R9")
      (libsource (lib "瑞臻信息") (part "XC6228"))
    )
    (comp (ref "U78")
      (value "XC6228")
      (footprint "SOT23_5P_0R95_1R6X2R9")
      (libsource (lib "瑞臻信息") (part "XC6228"))
    )
    (comp (ref "U79")
      (value "XC6228")
      (footprint "SOT23_5P_0R95_1R6X2R9")
      (libsource (lib "瑞臻信息") (part "XC6228"))
    )
    (comp (ref "U80")
      (value "XC6228")
      (footprint "SOT23_5P_0R95_1R6X2R9")
      (libsource (lib "瑞臻信息") (part "XC6228"))
    )
    (comp (ref "U81")
      (value "XC6228")
      (footprint "SOT23_5P_0R95_1R6X2R9")
      (libsource (lib "瑞臻信息") (part "XC6228"))
    )
    (comp (ref "U82")
      (value "XC6228")
      (footprint "SOT23_5P_0R95_1R6X2R9")
      (libsource (lib "瑞臻信息") (part "XC6228"))
    )
    (comp (ref "U83")
      (value "XC6228")
      (footprint "SOT23_5P_0R95_1R6X2R9")
      (libsource (lib "瑞臻信息") (part "XC6228"))
    )
    (comp (ref "U84")
      (value "XC6228")
      (footprint "SOT23_5P_0R95_1R6X2R9")
      (libsource (lib "瑞臻信息") (part "XC6228"))
    )
    (comp (ref "U85")
      (value "XC6228")
      (footprint "SOT23_5P_0R95_1R6X2R9")
      (libsource (lib "瑞臻信息") (part "XC6228"))
    )
    (comp (ref "U86")
      (value "XC6228")
      (footprint "SOT23_5P_0R95_1R6X2R9")
      (libsource (lib "瑞臻信息") (part "XC6228"))
    )
    (comp (ref "U87")
      (value "XC6228")
      (footprint "SOT23_5P_0R95_1R6X2R9")
      (libsource (lib "瑞臻信息") (part "XC6228"))
    )
    (comp (ref "U88")
      (value "XC6228")
      (footprint "SOT23_5P_0R95_1R6X2R9")
      (libsource (lib "瑞臻信息") (part "XC6228"))
    )
    (comp (ref "U89")
      (value "XC6228")
      (footprint "SOT23_5P_0R95_1R6X2R9")
      (libsource (lib "瑞臻信息") (part "XC6228"))
    )
    (comp (ref "U90")
      (value "XC6228")
      (footprint "SOT23_5P_0R95_1R6X2R9")
      (libsource (lib "瑞臻信息") (part "XC6228"))
    )
    (comp (ref "U91")
      (value "XC6228")
      (footprint "SOT23_5P_0R95_1R6X2R9")
      (libsource (lib "瑞臻信息") (part "XC6228"))
    )
    (comp (ref "U92")
      (value "LM317")
      (footprint "TO252_3P_2R3_6R2X6R7")
      (libsource (lib "瑞臻信息") (part "LM317-ADJ"))
    )
    (comp (ref "U93")
      (value "~")
      (footprint "TO252_3P_2R3_6R2X6R7")
      (libsource (lib "瑞臻信息") (part "LM317-ADJ"))
    )
    (comp (ref "U94")
      (value "~")
      (footprint "TO252_3P_2R3_6R2X6R7")
      (libsource (lib "瑞臻信息") (part "LM317-ADJ"))
    )
    (comp (ref "U95")
      (value "~")
      (footprint "TO252_3P_2R3_6R2X6R7")
      (libsource (lib "瑞臻信息") (part "LM317-ADJ"))
    )
    (comp (ref "U96")
      (value "~")
      (footprint "TO252_3P_2R3_6R2X6R7")
      (libsource (lib "瑞臻信息") (part "LM317-ADJ"))
    )
    (comp (ref "U97")
      (value "~")
      (footprint "TO252_3P_2R3_6R2X6R7")
      (libsource (lib "瑞臻信息") (part "LM317-ADJ"))
    )
    (comp (ref "U98")
      (value "~")
      (footprint "TO252_3P_2R3_6R2X6R7")
      (libsource (lib "瑞臻信息") (part "LM317-ADJ"))
    )
    (comp (ref "U99")
      (value "~")
      (footprint "TO252_3P_2R3_6R2X6R7")
      (libsource (lib "瑞臻信息") (part "LM317-ADJ"))
    )
    (comp (ref "U100") (value "~") (footprint "SOP_8P_1R27_3R9X4R9") (libsource (lib "瑞臻信息") (part "LM358")))
    (comp (ref "U101") (value "~") (footprint "SOP_8P_1R27_3R9X4R9") (libsource (lib "瑞臻信息") (part "LM358")))
    (comp (ref "U102") (value "~") (footprint "SOP_8P_1R27_3R9X4R9") (libsource (lib "瑞臻信息") (part "LM358")))
    (comp (ref "U103") (value "~") (footprint "SOP_8P_1R27_3R9X4R9") (libsource (lib "瑞臻信息") (part "LM358")))
    (comp (ref "U104")
      (value "~")
      (footprint "SOT23_5P_0R95_1R6X2R9")
      (libsource (lib "瑞臻信息") (part "INA180A"))
    )
    (comp (ref "U105")
      (value "~")
      (footprint "SOT23_5P_0R95_1R6X2R9")
      (libsource (lib "瑞臻信息") (part "INA180A"))
    )
    (comp (ref "U106")
      (value "~")
      (footprint "SOT23_5P_0R95_1R6X2R9")
      (libsource (lib "瑞臻信息") (part "INA180A"))
    )
    (comp (ref "U107")
      (value "~")
      (footprint "SOT23_5P_0R95_1R6X2R9")
      (libsource (lib "瑞臻信息") (part "INA180A"))
    )
    (comp (ref "U108")
      (value "~")
      (footprint "SOT23_5P_0R95_1R6X2R9")
      (libsource (lib "瑞臻信息") (part "INA180A"))
    )
    (comp (ref "U109")
      (value "~")
      (footprint "SOT23_5P_0R95_1R6X2R9")
      (libsource (lib "瑞臻信息") (part "INA180A"))
    )
    (comp (ref "U110")
      (value "~")
      (footprint "SOT23_5P_0R95_1R6X2R9")
      (libsource (lib "瑞臻信息") (part "INA180A"))
    )
    (comp (ref "U111")
      (value "~")
      (footprint "SOT23_5P_0R95_1R6X2R9")
      (libsource (lib "瑞臻信息") (part "INA180A"))
    )
    (comp (ref "U112")
      (value "~")
      (footprint "SOT23_5P_0R95_1R6X2R9")
      (libsource (lib "瑞臻信息") (part "INA180A"))
    )
    (comp (ref "U113")
      (value "~")
      (footprint "SOT23_5P_0R95_1R6X2R9")
      (libsource (lib "瑞臻信息") (part "INA180A"))
    )
    (comp (ref "U114")
      (value "~")
      (footprint "SOT23_5P_0R95_1R6X2R9")
      (libsource (lib "瑞臻信息") (part "INA180A"))
    )
    (comp (ref "U115")
      (value "~")
      (footprint "SOT23_5P_0R95_1R6X2R9")
      (libsource (lib "瑞臻信息") (part "INA180A"))
    )
    (comp (ref "U116")
      (value "~")
      (footprint "SOT23_5P_0R95_1R6X2R9")
      (libsource (lib "瑞臻信息") (part "INA180A"))
    )
    (comp (ref "U117")
      (value "~")
      (footprint "SOT23_5P_0R95_1R6X2R9")
      (libsource (lib "瑞臻信息") (part "INA180A"))
    )
    (comp (ref "U118")
      (value "~")
      (footprint "SOT23_5P_0R95_1R6X2R9")
      (libsource (lib "瑞臻信息") (part "INA180A"))
    )
    (comp (ref "U119")
      (value "~")
      (footprint "SOT23_5P_0R95_1R6X2R9")
      (libsource (lib "瑞臻信息") (part "INA180A"))
    )
  )
  (nets
    (net (code "1") (name "DAC1") (class "Default")
      (node (ref "U100") (pin "3") (pinfunction "3_3") (pintype "passive"))
      (node (ref "U100") (pin "5") (pinfunction "5_5") (pintype "passive"))
      (node (ref "U101") (pin "3") (pinfunction "3_3") (pintype "passive"))
      (node (ref "U101") (pin "5") (pinfunction "5_5") (pintype "passive"))
      (node (ref "U102") (pin "3") (pinfunction "3_3") (pintype "passive"))
      (node (ref "U102") (pin "5") (pinfunction "5_5") (pintype "passive"))
      (node (ref "U103") (pin "3") (pinfunction "3_3") (pintype "passive"))
      (node (ref "U103") (pin "5") (pinfunction "5_5") (pintype "passive"))
    )
    (net (code "2") (name "GND") (class "Default")
      (node (ref "C100") (pin "1") (pinfunction "1_1") (pintype "passive"))
      (node (ref "C101") (pin "1") (pinfunction "1_1") (pintype "passive"))
      (node (ref "C102") (pin "1") (pinfunction "1_1") (pintype "passive"))
      (node (ref "C103") (pin "1") (pinfunction "1_1") (pintype "passive"))
      (node (ref "C104") (pin "1") (pinfunction "1_1") (pintype "passive"))
      (node (ref "C105") (pin "1") (pinfunction "1_1") (pintype "passive"))
      (node (ref "C106") (pin "1") (pinfunction "1_1") (pintype "passive"))
      (node (ref "C107") (pin "1") (pinfunction "1_1") (pintype "passive"))
      (node (ref "C108") (pin "1") (pinfunction "1_1") (pintype "passive"))
      (node (ref "C109") (pin "1") (pinfunction "1_1") (pintype "passive"))
      (node (ref "C110") (pin "1") (pinfunction "1_1") (pintype "passive"))
      (node (ref "C111") (pin "1") (pinfunction "1_1") (pintype "passive"))
      (node (ref "C112") (pin "1") (pinfunction "1_1") (pintype "passive"))
      (node (ref "C113") (pin "1") (pinfunction "1_1") (pintype "passive"))
      (node (ref "C114") (pin "1") (pinfunction "1_1") (pintype "passive"))
      (node (ref "C115") (pin "1") (pinfunction "1_1") (pintype "passive"))
      (node (ref "C116") (pin "1") (pinfunction "1_1") (pintype "passive"))
      (node (ref "C117") (pin "1") (pinfunction "1_1") (pintype "passive"))
      (node (ref "C118") (pin "1") (pinfunction "1_1") (pintype "passive"))
      (node (ref "C119") (pin "1") (pinfunction "1_1") (pintype "passive"))
      (node (ref "C24") (pin "1") (pinfunction "1_1") (pintype "passive"))
      (node (ref "C25") (pin "1") (pinfunction "1_1") (pintype "passive"))
      (node (ref "C26") (pin "1") (pinfunction "1_1") (pintype "passive"))
      (node (ref "C27") (pin "1") (pinfunction "1_1") (pintype "passive"))
      (node (ref "C28") (pin "1") (pinfunction "1_1") (pintype "passive"))
      (node (ref "C29") (pin "1") (pinfunction "1_1") (pintype "passive"))
      (node (ref "C30") (pin "1") (pinfunction "1_1") (pintype "passive"))
      (node (ref "C31") (pin "1") (pinfunction "1_1") (pintype "passive"))
      (node (ref "C32") (pin "1") (pinfunction "1_1") (pintype "passive"))
      (node (ref "C33") (pin "1") (pinfunction "1_1") (pintype "passive"))
      (node (ref "C34") (pin "1") (pinfunction "1_1") (pintype "passive"))
      (node (ref "C35") (pin "1") (pinfunction "1_1") (pintype "passive"))
      (node (ref "C36") (pin "1") (pinfunction "1_1") (pintype "passive"))
      (node (ref "C37") (pin "1") (pinfunction "1_1") (pintype "passive"))
      (node (ref "C38") (pin "1") (pinfunction "1_1") (pintype "passive"))
      (node (ref "C39") (pin "1") (pinfunction "1_1") (pintype "passive"))
      (node (ref "C40") (pin "1") (pinfunction "1_1") (pintype "passive"))
      (node (ref "C41") (pin "1") (pinfunction "1_1") (pintype "passive"))
      (node (ref "C42") (pin "1") (pinfunction "1_1") (pintype "passive"))
      (node (ref "C43") (pin "1") (pinfunction "1_1") (pintype "passive"))
      (node (ref "C44") (pin "1") (pinfunction "1_1") (pintype "passive"))
      (node (ref "C45") (pin "1") (pinfunction "1_1") (pintype "passive"))
      (node (ref "C46") (pin "1") (pinfunction "1_1") (pintype "passive"))
      (node (ref "C47") (pin "1") (pinfunction "1_1") (pintype "passive"))
      (node (ref "C48") (pin "1") (pinfunction "1_1") (pintype "passive"))
      (node (ref "C49") (pin "1") (pinfunction "1_1") (pintype "passive"))
      (node (ref "C50") (pin "1") (pinfunction "1_1") (pintype "passive"))
      (node (ref "C51") (pin "1") (pinfunction "1_1") (pintype "passive"))
      (node (ref "C52") (pin "1") (pinfunction "1_1") (pintype "passive"))
      (node (ref "C53") (pin "1") (pinfunction "1_1") (pintype "passive"))
      (node (ref "C54") (pin "1") (pinfunction "1_1") (pintype "passive"))
      (node (ref "C55") (pin "1") (pinfunction "1_1") (pintype "passive"))
      (node (ref "C56") (pin "1") (pinfunction "1_1") (pintype "passive"))
      (node (ref "C57") (pin "1") (pinfunction "1_1") (pintype "passive"))
      (node (ref "C58") (pin "1") (pinfunction "1_1") (pintype "passive"))
      (node (ref "C59") (pin "1") (pinfunction "1_1") (pintype "passive"))
      (node (ref "C60") (pin "1") (pinfunction "1_1") (pintype "passive"))
      (node (ref "C61") (pin "1") (pinfunction "1_1") (pintype "passive"))
      (node (ref "C62") (pin "1") (pinfunction "1_1") (pintype "passive"))
      (node (ref "C63") (pin "1") (pinfunction "1_1") (pintype "passive"))
      (node (ref "C64") (pin "1") (pinfunction "1_1") (pintype "passive"))
      (node (ref "C65") (pin "1") (pinfunction "1_1") (pintype "passive"))
      (node (ref "C66") (pin "1") (pinfunction "1_1") (pintype "passive"))
      (node (ref "C67") (pin "1") (pinfunction "1_1") (pintype "passive"))
      (node (ref "C68") (pin "1") (pinfunction "1_1") (pintype "passive"))
      (node (ref "C69") (pin "1") (pinfunction "1_1") (pintype "passive"))
      (node (ref "C70") (pin "1") (pinfunction "1_1") (pintype "passive"))
      (node (ref "C71") (pin "1") (pinfunction "1_1") (pintype "passive"))
      (node (ref "C72") (pin "1") (pinfunction "1_1") (pintype "passive"))
      (node (ref "C73") (pin "1") (pinfunction "1_1") (pintype "passive"))
      (node (ref "C74") (pin "1") (pinfunction "1_1") (pintype "passive"))
      (node (ref "C75") (pin "1") (pinfunction "1_1") (pintype "passive"))
      (node (ref "C76") (pin "1") (pinfunction "1_1") (pintype "passive"))
      (node (ref "C77") (pin "1") (pinfunction "1_1") (pintype "passive"))
      (node (ref "C78") (pin "1") (pinfunction "1_1") (pintype "passive"))
      (node (ref "C79") (pin "1") (pinfunction "1_1") (pintype "passive"))
      (node (ref "C80") (pin "1") (pinfunction "1_1") (pintype "passive"))
      (node (ref "C81") (pin "1") (pinfunction "1_1") (pintype "passive"))
      (node (ref "C82") (pin "1") (pinfunction "1_1") (pintype "passive"))
      (node (ref "C83") (pin "1") (pinfunction "1_1") (pintype "passive"))
      (node (ref "C84") (pin "1") (pinfunction "1_1") (pintype "passive"))
      (node (ref "C85") (pin "1") (pinfunction "1_1") (pintype "passive"))
      (node (ref "C86") (pin "1") (pinfunction "1_1") (pintype "passive"))
      (node (ref "C87") (pin "1") (pinfunction "1_1") (pintype "passive"))
      (node (ref "C88") (pin "1") (pinfunction "1_1") (pintype "passive"))
      (node (ref "C89") (pin "1") (pinfunction "1_1") (pintype "passive"))
      (node (ref "C90") (pin "1") (pinfunction "1_1") (pintype "passive"))
      (node (ref "C91") (pin "1") (pinfunction "1_1") (pintype "passive"))
      (node (ref "C92") (pin "1") (pinfunction "1_1") (pintype "passive"))
      (node (ref "C93") (pin "1") (pinfunction "1_1") (pintype "passive"))
      (node (ref "C94") (pin "1") (pinfunction "1_1") (pintype "passive"))
      (node (ref "C95") (pin "1") (pinfunction "1_1") (pintype "passive"))
      (node (ref "C96") (pin "1") (pinfunction "1_1") (pintype "passive"))
      (node (ref "C97") (pin "1") (pinfunction "1_1") (pintype "passive"))
      (node (ref "C98") (pin "1") (pinfunction "1_1") (pintype "passive"))
      (node (ref "C99") (pin "1") (pinfunction "1_1") (pintype "passive"))
      (node (ref "D1") (pin "1") (pinfunction "A_1") (pintype "passive"))
      (node (ref "D10") (pin "1") (pinfunction "A_1") (pintype "passive"))
      (node (ref "D11") (pin "1") (pinfunction "A_1") (pintype "passive"))
      (node (ref "D12") (pin "1") (pinfunction "A_1") (pintype "passive"))
      (node (ref "D13") (pin "1") (pinfunction "A_1") (pintype "passive"))
      (node (ref "D14") (pin "1") (pinfunction "A_1") (pintype "passive"))
      (node (ref "D15") (pin "1") (pinfunction "A_1") (pintype "passive"))
      (node (ref "D16") (pin "1") (pinfunction "A_1") (pintype "passive"))
      (node (ref "D2") (pin "1") (pinfunction "A_1") (pintype "passive"))
      (node (ref "D3") (pin "1") (pinfunction "A_1") (pintype "passive"))
      (node (ref "D4") (pin "1") (pinfunction "A_1") (pintype "passive"))
      (node (ref "D5") (pin "1") (pinfunction "A_1") (pintype "passive"))
      (node (ref "D6") (pin "1") (pinfunction "A_1") (pintype "passive"))
      (node (ref "D7") (pin "1") (pinfunction "A_1") (pintype "passive"))
      (node (ref "D8") (pin "1") (pinfunction "A_1") (pintype "passive"))
      (node (ref "D9") (pin "1") (pinfunction "A_1") (pintype "passive"))
      (node (ref "Q15") (pin "2") (pinfunction "E_2") (pintype "passive"))
      (node (ref "Q16") (pin "2") (pinfunction "E_2") (pintype "passive"))
      (node (ref "Q17") (pin "2") (pinfunction "E_2") (pintype "passive"))
      (node (ref "Q18") (pin "2") (pinfunction "E_2") (pintype "passive"))
      (node (ref "Q19") (pin "2") (pinfunction "E_2") (pintype "passive"))
      (node (ref "Q20") (pin "2") (pinfunction "E_2") (pintype "passive"))
      (node (ref "Q21") (pin "2") (pinfunction "E_2") (pintype "passive"))
      (node (ref "Q22") (pin "2") (pinfunction "E_2") (pintype "passive"))
      (node (ref "U100") (pin "4") (pinfunction "V-_4") (pintype "passive"))
      (node (ref "U101") (pin "4") (pinfunction "V-_4") (pintype "passive"))
      (node (ref "U102") (pin "4") (pinfunction "V-_4") (pintype "passive"))
      (node (ref "U103") (pin "4") (pinfunction "V-_4") (pintype "passive"))
      (node (ref "U104") (pin "2") (pinfunction "GND_2") (pintype "passive"))
      (node (ref "U105") (pin "2") (pinfunction "GND_2") (pintype "passive"))
      (node (ref "U106") (pin "2") (pinfunction "GND_2") (pintype "passive"))
      (node (ref "U107") (pin "2") (pinfunction "GND_2") (pintype "passive"))
      (node (ref "U108") (pin "2") (pinfunction "GND_2") (pintype "passive"))
      (node (ref "U109") (pin "2") (pinfunction "GND_2") (pintype "passive"))
      (node (ref "U110") (pin "2") (pinfunction "GND_2") (pintype "passive"))
      (node (ref "U111") (pin "2") (pinfunction "GND_2") (pintype "passive"))
      (node (ref "U112") (pin "2") (pinfunction "GND_2") (pintype "passive"))
      (node (ref "U113") (pin "2") (pinfunction "GND_2") (pintype "passive"))
      (node (ref "U114") (pin "2") (pinfunction "GND_2") (pintype "passive"))
      (node (ref "U115") (pin "2") (pinfunction "GND_2") (pintype "passive"))
      (node (ref "U116") (pin "2") (pinfunction "GND_2") (pintype "passive"))
      (node (ref "U117") (pin "2") (pinfunction "GND_2") (pintype "passive"))
      (node (ref "U118") (pin "2") (pinfunction "GND_2") (pintype "passive"))
      (node (ref "U119") (pin "2") (pinfunction "GND_2") (pintype "passive"))
      (node (ref "U52") (pin "1") (pinfunction "GND_1") (pintype "passive"))
      (node (ref "U53") (pin "1") (pinfunction "GND_1") (pintype "passive"))
      (node (ref "U54") (pin "1") (pinfunction "GND_1") (pintype "passive"))
      (node (ref "U55") (pin "1") (pinfunction "GND_1") (pintype "passive"))
      (node (ref "U56") (pin "1") (pinfunction "GND_1") (pintype "passive"))
      (node (ref "U57") (pin "1") (pinfunction "GND_1") (pintype "passive"))
      (node (ref "U58") (pin "1") (pinfunction "GND_1") (pintype "passive"))
      (node (ref "U59") (pin "1") (pinfunction "GND_1") (pintype "passive"))
      (node (ref "U60") (pin "2") (pinfunction "GND_2") (pintype "passive"))
      (node (ref "U61") (pin "2") (pinfunction "GND_2") (pintype "passive"))
      (node (ref "U62") (pin "2") (pinfunction "GND_2") (pintype "passive"))
      (node (ref "U63") (pin "2") (pinfunction "GND_2") (pintype "passive"))
      (node (ref "U64") (pin "2") (pinfunction "GND_2") (pintype "passive"))
      (node (ref "U65") (pin "2") (pinfunction "GND_2") (pintype "passive"))
      (node (ref "U66") (pin "2") (pinfunction "GND_2") (pintype "passive"))
      (node (ref "U67") (pin "2") (pinfunction "GND_2") (pintype "passive"))
      (node (ref "U68") (pin "2") (pinfunction "GND_2") (pintype "passive"))
      (node (ref "U69") (pin "2") (pinfunction "GND_2") (pintype "passive"))
      (node (ref "U70") (pin "2") (pinfunction "GND_2") (pintype "passive"))
      (node (ref "U71") (pin "2") (pinfunction "GND_2") (pintype "passive"))
      (node (ref "U72") (pin "2") (pinfunction "GND_2") (pintype "passive"))
      (node (ref "U73") (pin "2") (pinfunction "GND_2") (pintype "passive"))
      (node (ref "U74") (pin "2") (pinfunction "GND_2") (pintype "passive"))
      (node (ref "U75") (pin "2") (pinfunction "GND_2") (pintype "passive"))
      (node (ref "U76") (pin "2") (pinfunction "GND_2") (pintype "passive"))
      (node (ref "U77") (pin "2") (pinfunction "GND_2") (pintype "passive"))
      (node (ref "U78") (pin "2") (pinfunction "GND_2") (pintype "passive"))
      (node (ref "U79") (pin "2") (pinfunction "GND_2") (pintype "passive"))
      (node (ref "U80") (pin "2") (pinfunction "GND_2") (pintype "passive"))
      (node (ref "U81") (pin "2") (pinfunction "GND_2") (pintype "passive"))
      (node (ref "U82") (pin "2") (pinfunction "GND_2") (pintype "passive"))
      (node (ref "U83") (pin "2") (pinfunction "GND_2") (pintype "passive"))
      (node (ref "U84") (pin "2") (pinfunction "GND_2") (pintype "passive"))
      (node (ref "U85") (pin "2") (pinfunction "GND_2") (pintype "passive"))
      (node (ref "U86") (pin "2") (pinfunction "GND_2") (pintype "passive"))
      (node (ref "U87") (pin "2") (pinfunction "GND_2") (pintype "passive"))
      (node (ref "U88") (pin "2") (pinfunction "GND_2") (pintype "passive"))
      (node (ref "U89") (pin "2") (pinfunction "GND_2") (pintype "passive"))
      (node (ref "U90") (pin "2") (pinfunction "GND_2") (pintype "passive"))
      (node (ref "U91") (pin "2") (pinfunction "GND_2") (pintype "passive"))
    )
    (net (code "3") (name "I_MA_0") (class "Default")
      (node (ref "D9") (pin "2") (pinfunction "K_2") (pintype "passive"))
      (node (ref "U112") (pin "1") (pinfunction "OUT_1") (pintype "passive"))
    )
    (net (code "4") (name "I_MA_1") (class "Default")
      (node (ref "D10") (pin "2") (pinfunction "K_2") (pintype "passive"))
      (node (ref "U113") (pin "1") (pinfunction "OUT_1") (pintype "passive"))
    )
    (net (code "5") (name "I_MA_2") (class "Default")
      (node (ref "D11") (pin "2") (pinfunction "K_2") (pintype "passive"))
      (node (ref "U114") (pin "1") (pinfunction "OUT_1") (pintype "passive"))
    )
    (net (code "6") (name "I_MA_3") (class "Default")
      (node (ref "D12") (pin "2") (pinfunction "K_2") (pintype "passive"))
      (node (ref "U115") (pin "1") (pinfunction "OUT_1") (pintype "passive"))
    )
    (net (code "7") (name "I_MA_4") (class "Default")
      (node (ref "D13") (pin "2") (pinfunction "K_2") (pintype "passive"))
      (node (ref "U116") (pin "1") (pinfunction "OUT_1") (pintype "passive"))
    )
    (net (code "8") (name "I_MA_5") (class "Default")
      (node (ref "D14") (pin "2") (pinfunction "K_2") (pintype "passive"))
      (node (ref "U117") (pin "1") (pinfunction "OUT_1") (pintype "passive"))
    )
    (net (code "9") (name "I_MA_6") (class "Default")
      (node (ref "D15") (pin "2") (pinfunction "K_2") (pintype "passive"))
      (node (ref "U118") (pin "1") (pinfunction "OUT_1") (pintype "passive"))
    )
    (net (code "10") (name "I_MA_7") (class "Default")
      (node (ref "D16") (pin "2") (pinfunction "K_2") (pintype "passive"))
      (node (ref "U119") (pin "1") (pinfunction "OUT_1") (pintype "passive"))
    )
    (net (code "11") (name "I_UA_0") (class "Default")
      (node (ref "D1") (pin "2") (pinfunction "K_2") (pintype "passive"))
      (node (ref "U104") (pin "1") (pinfunction "OUT_1") (pintype "passive"))
    )
    (net (code "12") (name "I_UA_1") (class "Default")
      (node (ref "D2") (pin "2") (pinfunction "K_2") (pintype "passive"))
      (node (ref "U105") (pin "1") (pinfunction "OUT_1") (pintype "passive"))
    )
    (net (code "13") (name "I_UA_2") (class "Default")
      (node (ref "D3") (pin "2") (pinfunction "K_2") (pintype "passive"))
      (node (ref "U106") (pin "1") (pinfunction "OUT_1") (pintype "passive"))
    )
    (net (code "14") (name "I_UA_3") (class "Default")
      (node (ref "D4") (pin "2") (pinfunction "K_2") (pintype "passive"))
      (node (ref "U107") (pin "1") (pinfunction "OUT_1") (pintype "passive"))
    )
    (net (code "15") (name "I_UA_4") (class "Default")
      (node (ref "D5") (pin "2") (pinfunction "K_2") (pintype "passive"))
      (node (ref "U108") (pin "1") (pinfunction "OUT_1") (pintype "passive"))
    )
    (net (code "16") (name "I_UA_5") (class "Default")
      (node (ref "D6") (pin "2") (pinfunction "K_2") (pintype "passive"))
      (node (ref "U109") (pin "1") (pinfunction "OUT_1") (pintype "passive"))
    )
    (net (code "17") (name "I_UA_6") (class "Default")
      (node (ref "D7") (pin "2") (pinfunction "K_2") (pintype "passive"))
      (node (ref "U110") (pin "1") (pinfunction "OUT_1") (pintype "passive"))
    )
    (net (code "18") (name "I_UA_7") (class "Default")
      (node (ref "D8") (pin "2") (pinfunction "K_2") (pintype "passive"))
      (node (ref "U111") (pin "1") (pinfunction "OUT_1") (pintype "passive"))
    )
    (net (code "19") (name "Net-(Q7-D)") (class "Default")
      (node (ref "Q7") (pin "3") (pinfunction "D_3") (pintype "passive"))
      (node (ref "R242") (pin "1") (pinfunction "1_1") (pintype "passive"))
      (node (ref "U104") (pin "3") (pinfunction "IN+_3") (pintype "passive"))
      (node (ref "U112") (pin "3") (pinfunction "IN+_3") (pintype "passive"))
    )
    (net (code "20") (name "Net-(Q7-S)") (class "Default")
      (node (ref "C105") (pin "2") (pinfunction "2_2") (pintype "passive"))
      (node (ref "Q7") (pin "2") (pinfunction "S_2") (pintype "passive"))
      (node (ref "R210") (pin "2") (pinfunction "2_2") (pintype "passive"))
      (node (ref "R226") (pin "1") (pinfunction "1_1") (pintype "passive"))
      (node (ref "U92") (pin "4") (pinfunction "OUT_4") (pintype "passive"))
    )
    (net (code "21") (name "Net-(Q8-D)") (class "Default")
      (node (ref "Q8") (pin "3") (pinfunction "D_3") (pintype "passive"))
      (node (ref "R243") (pin "1") (pinfunction "1_1") (pintype "passive"))
      (node (ref "U105") (pin "3") (pinfunction "IN+_3") (pintype "passive"))
      (node (ref "U113") (pin "3") (pinfunction "IN+_3") (pintype "passive"))
    )
    (net (code "22") (name "Net-(Q8-S)") (class "Default")
      (node (ref "C107") (pin "2") (pinfunction "2_2") (pintype "passive"))
      (node (ref "Q8") (pin "2") (pinfunction "S_2") (pintype "passive"))
      (node (ref "R211") (pin "2") (pinfunction "2_2") (pintype "passive"))
      (node (ref "R227") (pin "1") (pinfunction "1_1") (pintype "passive"))
      (node (ref "U93") (pin "4") (pinfunction "OUT_4") (pintype "passive"))
    )
    (net (code "23") (name "Net-(Q9-D)") (class "Default")
      (node (ref "Q9") (pin "3") (pinfunction "D_3") (pintype "passive"))
      (node (ref "R244") (pin "1") (pinfunction "1_1") (pintype "passive"))
      (node (ref "U106") (pin "3") (pinfunction "IN+_3") (pintype "passive"))
      (node (ref "U114") (pin "3") (pinfunction "IN+_3") (pintype "passive"))
    )
    (net (code "24") (name "Net-(Q9-S)") (class "Default")
      (node (ref "C109") (pin "2") (pinfunction "2_2") (pintype "passive"))
      (node (ref "Q9") (pin "2") (pinfunction "S_2") (pintype "passive"))
      (node (ref "R212") (pin "2") (pinfunction "2_2") (pintype "passive"))
      (node (ref "R228") (pin "1") (pinfunction "1_1") (pintype "passive"))
      (node (ref "U94") (pin "4") (pinfunction "OUT_4") (pintype "passive"))
    )
    (net (code "25") (name "Net-(Q10-D)") (class "Default")
      (node (ref "Q10") (pin "3") (pinfunction "D_3") (pintype "passive"))
      (node (ref "R245") (pin "1") (pinfunction "1_1") (pintype "passive"))
      (node (ref "U107") (pin "3") (pinfunction "IN+_3") (pintype "passive"))
      (node (ref "U115") (pin "3") (pinfunction "IN+_3") (pintype "passive"))
    )
    (net (code "26") (name "Net-(Q10-G)") (class "Default")
      (node (ref "Q10") (pin "1") (pinfunction "G_1") (pintype "passive"))
      (node (ref "Q18") (pin "3") (pinfunction "C_3") (pintype "passive"))
      (node (ref "R229") (pin "2") (pinfunction "2_2") (pintype "passive"))
    )
    (net (code "27") (name "Net-(Q10-S)") (class "Default")
      (node (ref "C111") (pin "2") (pinfunction "2_2") (pintype "passive"))
      (node (ref "Q10") (pin "2") (pinfunction "S_2") (pintype "passive"))
      (node (ref "R213") (pin "2") (pinfunction "2_2") (pintype "passive"))
      (node (ref "R229") (pin "1") (pinfunction "1_1") (pintype "passive"))
      (node (ref "U95") (pin "4") (pinfunction "OUT_4") (pintype "passive"))
    )
    (net (code "28") (name "Net-(Q11-D)") (class "Default")
      (node (ref "Q11") (pin "3") (pinfunction "D_3") (pintype "passive"))
      (node (ref "R246") (pin "1") (pinfunction "1_1") (pintype "passive"))
      (node (ref "U108") (pin "3") (pinfunction "IN+_3") (pintype "passive"))
      (node (ref "U116") (pin "3") (pinfunction "IN+_3") (pintype "passive"))
    )
    (net (code "29") (name "Net-(Q11-G)") (class "Default")
      (node (ref "Q11") (pin "1") (pinfunction "G_1") (pintype "passive"))
      (node (ref "Q19") (pin "3") (pinfunction "C_3") (pintype "passive"))
      (node (ref "R230") (pin "2") (pinfunction "2_2") (pintype "passive"))
    )
    (net (code "30") (name "Net-(Q11-S)") (class "Default")
      (node (ref "C113") (pin "2") (pinfunction "2_2") (pintype "passive"))
      (node (ref "Q11") (pin "2") (pinfunction "S_2") (pintype "passive"))
      (node (ref "R214") (pin "2") (pinfunction "2_2") (pintype "passive"))
      (node (ref "R230") (pin "1") (pinfunction "1_1") (pintype "passive"))
      (node (ref "U96") (pin "4") (pinfunction "OUT_4") (pintype "passive"))
    )
    (net (code "31") (name "Net-(Q12-D)") (class "Default")
      (node (ref "Q12") (pin "3") (pinfunction "D_3") (pintype "passive"))
      (node (ref "R247") (pin "1") (pinfunction "1_1") (pintype "passive"))
      (node (ref "U109") (pin "3") (pinfunction "IN+_3") (pintype "passive"))
      (node (ref "U117") (pin "3") (pinfunction "IN+_3") (pintype "passive"))
    )
    (net (code "32") (name "Net-(Q12-G)") (class "Default")
      (node (ref "Q12") (pin "1") (pinfunction "G_1") (pintype "passive"))
      (node (ref "Q20") (pin "3") (pinfunction "C_3") (pintype "passive"))
      (node (ref "R231") (pin "2") (pinfunction "2_2") (pintype "passive"))
    )
    (net (code "33") (name "Net-(Q12-S)") (class "Default")
      (node (ref "C115") (pin "2") (pinfunction "2_2") (pintype "passive"))
      (node (ref "Q12") (pin "2") (pinfunction "S_2") (pintype "passive"))
      (node (ref "R215") (pin "2") (pinfunction "2_2") (pintype "passive"))
      (node (ref "R231") (pin "1") (pinfunction "1_1") (pintype "passive"))
      (node (ref "U97") (pin "4") (pinfunction "OUT_4") (pintype "passive"))
    )
    (net (code "34") (name "Net-(Q13-D)") (class "Default")
      (node (ref "Q13") (pin "3") (pinfunction "D_3") (pintype "passive"))
      (node (ref "R248") (pin "1") (pinfunction "1_1") (pintype "passive"))
      (node (ref "U110") (pin "3") (pinfunction "IN+_3") (pintype "passive"))
      (node (ref "U118") (pin "3") (pinfunction "IN+_3") (pintype "passive"))
    )
    (net (code "35") (name "Net-(Q13-G)") (class "Default")
      (node (ref "Q13") (pin "1") (pinfunction "G_1") (pintype "passive"))
      (node (ref "Q21") (pin "3") (pinfunction "C_3") (pintype "passive"))
      (node (ref "R232") (pin "2") (pinfunction "2_2") (pintype "passive"))
    )
    (net (code "36") (name "Net-(Q13-S)") (class "Default")
      (node (ref "C117") (pin "2") (pinfunction "2_2") (pintype "passive"))
      (node (ref "Q13") (pin "2") (pinfunction "S_2") (pintype "passive"))
      (node (ref "R216") (pin "2") (pinfunction "2_2") (pintype "passive"))
      (node (ref "R232") (pin "1") (pinfunction "1_1") (pintype "passive"))
      (node (ref "U98") (pin "4") (pinfunction "OUT_4") (pintype "passive"))
    )
    (net (code "37") (name "Net-(Q14-D)") (class "Default")
      (node (ref "Q14") (pin "3") (pinfunction "D_3") (pintype "passive"))
      (node (ref "R249") (pin "1") (pinfunction "1_1") (pintype "passive"))
      (node (ref "U111") (pin "3") (pinfunction "IN+_3") (pintype "passive"))
      (node (ref "U119") (pin "3") (pinfunction "IN+_3") (pintype "passive"))
    )
    (net (code "38") (name "Net-(Q14-G)") (class "Default")
      (node (ref "Q14") (pin "1") (pinfunction "G_1") (pintype "passive"))
      (node (ref "Q22") (pin "3") (pinfunction "C_3") (pintype "passive"))
      (node (ref "R233") (pin "2") (pinfunction "2_2") (pintype "passive"))
    )
    (net (code "39") (name "Net-(Q14-S)") (class "Default")
      (node (ref "C119") (pin "2") (pinfunction "2_2") (pintype "passive"))
      (node (ref "Q14") (pin "2") (pinfunction "S_2") (pintype "passive"))
      (node (ref "R217") (pin "2") (pinfunction "2_2") (pintype "passive"))
      (node (ref "R233") (pin "1") (pinfunction "1_1") (pintype "passive"))
      (node (ref "U99") (pin "4") (pinfunction "OUT_4") (pintype "passive"))
    )
    (net (code "40") (name "Net-(Q15-B)") (class "Default")
      (node (ref "Q15") (pin "1") (pinfunction "B_1") (pintype "passive"))
      (node (ref "R234") (pin "1") (pinfunction "1_1") (pintype "passive"))
    )
    (net (code "41") (name "Net-(Q15-C)") (class "Default")
      (node (ref "Q15") (pin "3") (pinfunction "C_3") (pintype "passive"))
      (node (ref "Q7") (pin "1") (pinfunction "G_1") (pintype "passive"))
      (node (ref "R226") (pin "2") (pinfunction "2_2") (pintype "passive"))
    )
    (net (code "42") (name "Net-(Q16-B)") (class "Default")
      (node (ref "Q16") (pin "1") (pinfunction "B_1") (pintype "passive"))
      (node (ref "R235") (pin "1") (pinfunction "1_1") (pintype "passive"))
    )
    (net (code "43") (name "Net-(Q16-C)") (class "Default")
      (node (ref "Q16") (pin "3") (pinfunction "C_3") (pintype "passive"))
      (node (ref "Q8") (pin "1") (pinfunction "G_1") (pintype "passive"))
      (node (ref "R227") (pin "2") (pinfunction "2_2") (pintype "passive"))
    )
    (net (code "44") (name "Net-(Q17-B)") (class "Default")
      (node (ref "Q17") (pin "1") (pinfunction "B_1") (pintype "passive"))
      (node (ref "R236") (pin "1") (pinfunction "1_1") (pintype "passive"))
    )
    (net (code "45") (name "Net-(Q17-C)") (class "Default")
      (node (ref "Q17") (pin "3") (pinfunction "C_3") (pintype "passive"))
      (node (ref "Q9") (pin "1") (pinfunction "G_1") (pintype "passive"))
      (node (ref "R228") (pin "2") (pinfunction "2_2") (pintype "passive"))
    )
    (net (code "46") (name "Net-(Q18-B)") (class "Default")
      (node (ref "Q18") (pin "1") (pinfunction "B_1") (pintype "passive"))
      (node (ref "R237") (pin "1") (pinfunction "1_1") (pintype "passive"))
    )
    (net (code "47") (name "Net-(Q19-B)") (class "Default")
      (node (ref "Q19") (pin "1") (pinfunction "B_1") (pintype "passive"))
      (node (ref "R238") (pin "1") (pinfunction "1_1") (pintype "passive"))
    )
    (net (code "48") (name "Net-(Q20-B)") (class "Default")
      (node (ref "Q20") (pin "1") (pinfunction "B_1") (pintype "passive"))
      (node (ref "R239") (pin "1") (pinfunction "1_1") (pintype "passive"))
    )
    (net (code "49") (name "Net-(Q21-B)") (class "Default")
      (node (ref "Q21") (pin "1") (pinfunction "B_1") (pintype "passive"))
      (node (ref "R240") (pin "1") (pinfunction "1_1") (pintype "passive"))
    )
    (net (code "50") (name "Net-(Q22-B)") (class "Default")
      (node (ref "Q22") (pin "1") (pinfunction "B_1") (pintype "passive"))
      (node (ref "R241") (pin "1") (pinfunction "1_1") (pintype "passive"))
    )
    (net (code "51") (name "Net-(R218-Pad1)") (class "Default")
      (node (ref "R218") (pin "1") (pinfunction "1_1") (pintype "passive"))
      (node (ref "U100") (pin "1") (pinfunction "1_1") (pintype "passive"))
      (node (ref "U100") (pin "2") (pinfunction "2_2") (pintype "passive"))
    )
    (net (code "52") (name "Net-(R219-Pad1)") (class "Default")
      (node (ref "R219") (pin "1") (pinfunction "1_1") (pintype "passive"))
      (node (ref "U100") (pin "6") (pinfunction "6_6") (pintype "passive"))
      (node (ref "U100") (pin "7") (pinfunction "7_7") (pintype "passive"))
    )
    (net (code "53") (name "Net-(R220-Pad1)") (class "Default")
      (node (ref "R220") (pin "1") (pinfunction "1_1") (pintype "passive"))
      (node (ref "U101") (pin "1") (pinfunction "1_1") (pintype "passive"))
      (node (ref "U101") (pin "2") (pinfunction "2_2") (pintype "passive"))
    )
    (net (code "54") (name "Net-(R221-Pad1)") (class "Default")
      (node (ref "R221") (pin "1") (pinfunction "1_1") (pintype "passive"))
      (node (ref "U101") (pin "6") (pinfunction "6_6") (pintype "passive"))
      (node (ref "U101") (pin "7") (pinfunction "7_7") (pintype "passive"))
    )
    (net (code "55") (name "Net-(R222-Pad1)") (class "Default")
      (node (ref "R222") (pin "1") (pinfunction "1_1") (pintype "passive"))
      (node (ref "U102") (pin "1") (pinfunction "1_1") (pintype "passive"))
      (node (ref "U102") (pin "2") (pinfunction "2_2") (pintype "passive"))
    )
    (net (code "56") (name "Net-(R223-Pad1)") (class "Default")
      (node (ref "R223") (pin "1") (pinfunction "1_1") (pintype "passive"))
      (node (ref "U102") (pin "6") (pinfunction "6_6") (pintype "passive"))
      (node (ref "U102") (pin "7") (pinfunction "7_7") (pintype "passive"))
    )
    (net (code "57") (name "Net-(R224-Pad1)") (class "Default")
      (node (ref "R224") (pin "1") (pinfunction "1_1") (pintype "passive"))
      (node (ref "U103") (pin "1") (pinfunction "1_1") (pintype "passive"))
      (node (ref "U103") (pin "2") (pinfunction "2_2") (pintype "passive"))
    )
    (net (code "58") (name "Net-(R225-Pad1)") (class "Default")
      (node (ref "R225") (pin "1") (pinfunction "1_1") (pintype "passive"))
      (node (ref "U103") (pin "6") (pinfunction "6_6") (pintype "passive"))
      (node (ref "U103") (pin "7") (pinfunction "7_7") (pintype "passive"))
    )
    (net (code "59") (name "Net-(U92-ADJ)") (class "Default")
      (node (ref "R210") (pin "1") (pinfunction "1_1") (pintype "passive"))
      (node (ref "R218") (pin "2") (pinfunction "2_2") (pintype "passive"))
      (node (ref "U92") (pin "1") (pinfunction "ADJ_1") (pintype "passive"))
    )
    (net (code "60") (name "Net-(U93-ADJ)") (class "Default")
      (node (ref "R211") (pin "1") (pinfunction "1_1") (pintype "passive"))
      (node (ref "R219") (pin "2") (pinfunction "2_2") (pintype "passive"))
      (node (ref "U93") (pin "1") (pinfunction "ADJ_1") (pintype "passive"))
    )
    (net (code "61") (name "Net-(U94-ADJ)") (class "Default")
      (node (ref "R212") (pin "1") (pinfunction "1_1") (pintype "passive"))
      (node (ref "R220") (pin "2") (pinfunction "2_2") (pintype "passive"))
      (node (ref "U94") (pin "1") (pinfunction "ADJ_1") (pintype "passive"))
    )
    (net (code "62") (name "Net-(U95-ADJ)") (class "Default")
      (node (ref "R213") (pin "1") (pinfunction "1_1") (pintype "passive"))
      (node (ref "R221") (pin "2") (pinfunction "2_2") (pintype "passive"))
      (node (ref "U95") (pin "1") (pinfunction "ADJ_1") (pintype "passive"))
    )
    (net (code "63") (name "Net-(U96-ADJ)") (class "Default")
      (node (ref "R214") (pin "1") (pinfunction "1_1") (pintype "passive"))
      (node (ref "R222") (pin "2") (pinfunction "2_2") (pintype "passive"))
      (node (ref "U96") (pin "1") (pinfunction "ADJ_1") (pintype "passive"))
    )
    (net (code "64") (name "Net-(U97-ADJ)") (class "Default")
      (node (ref "R215") (pin "1") (pinfunction "1_1") (pintype "passive"))
      (node (ref "R223") (pin "2") (pinfunction "2_2") (pintype "passive"))
      (node (ref "U97") (pin "1") (pinfunction "ADJ_1") (pintype "passive"))
    )
    (net (code "65") (name "Net-(U98-ADJ)") (class "Default")
      (node (ref "R216") (pin "1") (pinfunction "1_1") (pintype "passive"))
      (node (ref "R224") (pin "2") (pinfunction "2_2") (pintype "passive"))
      (node (ref "U98") (pin "1") (pinfunction "ADJ_1") (pintype "passive"))
    )
    (net (code "66") (name "Net-(U99-ADJ)") (class "Default")
      (node (ref "R217") (pin "1") (pinfunction "1_1") (pintype "passive"))
      (node (ref "R225") (pin "2") (pinfunction "2_2") (pintype "passive"))
      (node (ref "U99") (pin "1") (pinfunction "ADJ_1") (pintype "passive"))
    )
    (net (code "67") (name "POWER_EN0") (class "Default")
      (node (ref "R234") (pin "2") (pinfunction "2_2") (pintype "passive"))
      (node (ref "U60") (pin "3") (pinfunction "EN_3") (pintype "passive"))
      (node (ref "U68") (pin "3") (pinfunction "EN_3") (pintype "passive"))
      (node (ref "U76") (pin "3") (pinfunction "EN_3") (pintype "passive"))
      (node (ref "U84") (pin "3") (pinfunction "EN_3") (pintype "passive"))
    )
    (net (code "68") (name "POWER_EN1") (class "Default")
      (node (ref "R235") (pin "2") (pinfunction "2_2") (pintype "passive"))
      (node (ref "U61") (pin "3") (pinfunction "EN_3") (pintype "passive"))
      (node (ref "U69") (pin "3") (pinfunction "EN_3") (pintype "passive"))
      (node (ref "U77") (pin "3") (pinfunction "EN_3") (pintype "passive"))
      (node (ref "U85") (pin "3") (pinfunction "EN_3") (pintype "passive"))
    )
    (net (code "69") (name "POWER_EN2") (class "Default")
      (node (ref "R236") (pin "2") (pinfunction "2_2") (pintype "passive"))
      (node (ref "U62") (pin "3") (pinfunction "EN_3") (pintype "passive"))
      (node (ref "U70") (pin "3") (pinfunction "EN_3") (pintype "passive"))
      (node (ref "U78") (pin "3") (pinfunction "EN_3") (pintype "passive"))
      (node (ref "U86") (pin "3") (pinfunction "EN_3") (pintype "passive"))
    )
    (net (code "70") (name "POWER_EN3") (class "Default")
      (node (ref "R237") (pin "2") (pinfunction "2_2") (pintype "passive"))
      (node (ref "U63") (pin "3") (pinfunction "EN_3") (pintype "passive"))
      (node (ref "U71") (pin "3") (pinfunction "EN_3") (pintype "passive"))
      (node (ref "U79") (pin "3") (pinfunction "EN_3") (pintype "passive"))
      (node (ref "U87") (pin "3") (pinfunction "EN_3") (pintype "passive"))
    )
    (net (code "71") (name "POWER_EN4") (class "Default")
      (node (ref "R238") (pin "2") (pinfunction "2_2") (pintype "passive"))
      (node (ref "U64") (pin "3") (pinfunction "EN_3") (pintype "passive"))
      (node (ref "U72") (pin "3") (pinfunction "EN_3") (pintype "passive"))
      (node (ref "U80") (pin "3") (pinfunction "EN_3") (pintype "passive"))
      (node (ref "U88") (pin "3") (pinfunction "EN_3") (pintype "passive"))
    )
    (net (code "72") (name "POWER_EN5") (class "Default")
      (node (ref "R239") (pin "2") (pinfunction "2_2") (pintype "passive"))
      (node (ref "U65") (pin "3") (pinfunction "EN_3") (pintype "passive"))
      (node (ref "U73") (pin "3") (pinfunction "EN_3") (pintype "passive"))
      (node (ref "U81") (pin "3") (pinfunction "EN_3") (pintype "passive"))
      (node (ref "U89") (pin "3") (pinfunction "EN_3") (pintype "passive"))
    )
    (net (code "73") (name "POWER_EN6") (class "Default")
      (node (ref "R240") (pin "2") (pinfunction "2_2") (pintype "passive"))
      (node (ref "U66") (pin "3") (pinfunction "EN_3") (pintype "passive"))
      (node (ref "U74") (pin "3") (pinfunction "EN_3") (pintype "passive"))
      (node (ref "U82") (pin "3") (pinfunction "EN_3") (pintype "passive"))
      (node (ref "U90") (pin "3") (pinfunction "EN_3") (pintype "passive"))
    )
    (net (code "74") (name "POWER_EN7") (class "Default")
      (node (ref "R241") (pin "2") (pinfunction "2_2") (pintype "passive"))
      (node (ref "U67") (pin "3") (pinfunction "EN_3") (pintype "passive"))
      (node (ref "U75") (pin "3") (pinfunction "EN_3") (pintype "passive"))
      (node (ref "U83") (pin "3") (pinfunction "EN_3") (pintype "passive"))
      (node (ref "U91") (pin "3") (pinfunction "EN_3") (pintype "passive"))
    )
    (net (code "75") (name "VCC+1V8_0") (class "Default")
      (node (ref "C48") (pin "2") (pinfunction "2_2") (pintype "passive"))
      (node (ref "U60") (pin "5") (pinfunction "OUT_5") (pintype "passive"))
    )
    (net (code "76") (name "VCC+1V8_1") (class "Default")
      (node (ref "C49") (pin "2") (pinfunction "2_2") (pintype "passive"))
      (node (ref "U61") (pin "5") (pinfunction "OUT_5") (pintype "passive"))
    )
    (net (code "77") (name "VCC+1V8_2") (class "Default")
      (node (ref "C50") (pin "2") (pinfunction "2_2") (pintype "passive"))
      (node (ref "U62") (pin "5") (pinfunction "OUT_5") (pintype "passive"))
    )
    (net (code "78") (name "VCC+1V8_3") (class "Default")
      (node (ref "C51") (pin "2") (pinfunction "2_2") (pintype "passive"))
      (node (ref "U63") (pin "5") (pinfunction "OUT_5") (pintype "passive"))
    )
    (net (code "79") (name "VCC+1V8_4") (class "Default")
      (node (ref "C52") (pin "2") (pinfunction "2_2") (pintype "passive"))
      (node (ref "U64") (pin "5") (pinfunction "OUT_5") (pintype "passive"))
    )
    (net (code "80") (name "VCC+1V8_5") (class "Default")
      (node (ref "C53") (pin "2") (pinfunction "2_2") (pintype "passive"))
      (node (ref "U65") (pin "5") (pinfunction "OUT_5") (pintype "passive"))
    )
    (net (code "81") (name "VCC+1V8_6") (class "Default")
      (node (ref "C54") (pin "2") (pinfunction "2_2") (pintype "passive"))
      (node (ref "U66") (pin "5") (pinfunction "OUT_5") (pintype "passive"))
    )
    (net (code "82") (name "VCC+1V8_7") (class "Default")
      (node (ref "C55") (pin "2") (pinfunction "2_2") (pintype "passive"))
      (node (ref "U67") (pin "5") (pinfunction "OUT_5") (pintype "passive"))
    )
    (net (code "83") (name "VCC+2V5_0") (class "Default")
      (node (ref "C64") (pin "2") (pinfunction "2_2") (pintype "passive"))
      (node (ref "U68") (pin "5") (pinfunction "OUT_5") (pintype "passive"))
    )
    (net (code "84") (name "VCC+2V5_1") (class "Default")
      (node (ref "C65") (pin "2") (pinfunction "2_2") (pintype "passive"))
      (node (ref "U69") (pin "5") (pinfunction "OUT_5") (pintype "passive"))
    )
    (net (code "85") (name "VCC+2V5_2") (class "Default")
      (node (ref "C66") (pin "2") (pinfunction "2_2") (pintype "passive"))
      (node (ref "U70") (pin "5") (pinfunction "OUT_5") (pintype "passive"))
    )
    (net (code "86") (name "VCC+2V5_3") (class "Default")
      (node (ref "C67") (pin "2") (pinfunction "2_2") (pintype "passive"))
      (node (ref "U71") (pin "5") (pinfunction "OUT_5") (pintype "passive"))
    )
    (net (code "87") (name "VCC+2V5_4") (class "Default")
      (node (ref "C68") (pin "2") (pinfunction "2_2") (pintype "passive"))
      (node (ref "U72") (pin "5") (pinfunction "OUT_5") (pintype "passive"))
    )
    (net (code "88") (name "VCC+2V5_5") (class "Default")
      (node (ref "C69") (pin "2") (pinfunction "2_2") (pintype "passive"))
      (node (ref "U73") (pin "5") (pinfunction "OUT_5") (pintype "passive"))
    )
    (net (code "89") (name "VCC+2V5_6") (class "Default")
      (node (ref "C70") (pin "2") (pinfunction "2_2") (pintype "passive"))
      (node (ref "U74") (pin "5") (pinfunction "OUT_5") (pintype "passive"))
    )
    (net (code "90") (name "VCC+2V5_7") (class "Default")
      (node (ref "C71") (pin "2") (pinfunction "2_2") (pintype "passive"))
      (node (ref "U75") (pin "5") (pinfunction "OUT_5") (pintype "passive"))
    )
    (net (code "91") (name "VCC+3V0_0") (class "Default")
      (node (ref "C80") (pin "2") (pinfunction "2_2") (pintype "passive"))
      (node (ref "U76") (pin "5") (pinfunction "OUT_5") (pintype "passive"))
    )
    (net (code "92") (name "VCC+3V0_1") (class "Default")
      (node (ref "C81") (pin "2") (pinfunction "2_2") (pintype "passive"))
      (node (ref "U77") (pin "5") (pinfunction "OUT_5") (pintype "passive"))
    )
    (net (code "93") (name "VCC+3V0_2") (class "Default")
      (node (ref "C82") (pin "2") (pinfunction "2_2") (pintype "passive"))
      (node (ref "U78") (pin "5") (pinfunction "OUT_5") (pintype "passive"))
    )
    (net (code "94") (name "VCC+3V0_3") (class "Default")
      (node (ref "C83") (pin "2") (pinfunction "2_2") (pintype "passive"))
      (node (ref "U79") (pin "5") (pinfunction "OUT_5") (pintype "passive"))
    )
    (net (code "95") (name "VCC+3V0_4") (class "Default")
      (node (ref "C84") (pin "2") (pinfunction "2_2") (pintype "passive"))
      (node (ref "U80") (pin "5") (pinfunction "OUT_5") (pintype "passive"))
    )
    (net (code "96") (name "VCC+3V0_5") (class "Default")
      (node (ref "C85") (pin "2") (pinfunction "2_2") (pintype "passive"))
      (node (ref "U81") (pin "5") (pinfunction "OUT_5") (pintype "passive"))
    )
    (net (code "97") (name "VCC+3V0_6") (class "Default")
      (node (ref "C86") (pin "2") (pinfunction "2_2") (pintype "passive"))
      (node (ref "U82") (pin "5") (pinfunction "OUT_5") (pintype "passive"))
    )
    (net (code "98") (name "VCC+3V0_7") (class "Default")
      (node (ref "C87") (pin "2") (pinfunction "2_2") (pintype "passive"))
      (node (ref "U83") (pin "5") (pinfunction "OUT_5") (pintype "passive"))
    )
    (net (code "99") (name "VCC+3V3_0") (class "Default")
      (node (ref "C96") (pin "2") (pinfunction "2_2") (pintype "passive"))
      (node (ref "U84") (pin "5") (pinfunction "OUT_5") (pintype "passive"))
    )
    (net (code "100") (name "VCC+3V3_1") (class "Default")
      (node (ref "C97") (pin "2") (pinfunction "2_2") (pintype "passive"))
      (node (ref "U85") (pin "5") (pinfunction "OUT_5") (pintype "passive"))
    )
    (net (code "101") (name "VCC+3V3_2") (class "Default")
      (node (ref "C98") (pin "2") (pinfunction "2_2") (pintype "passive"))
      (node (ref "U86") (pin "5") (pinfunction "OUT_5") (pintype "passive"))
    )
    (net (code "102") (name "VCC+3V3_3") (class "Default")
      (node (ref "C99") (pin "2") (pinfunction "2_2") (pintype "passive"))
      (node (ref "U87") (pin "5") (pinfunction "OUT_5") (pintype "passive"))
    )
    (net (code "103") (name "VCC+3V3_4") (class "Default")
      (node (ref "C100") (pin "2") (pinfunction "2_2") (pintype "passive"))
      (node (ref "U88") (pin "5") (pinfunction "OUT_5") (pintype "passive"))
    )
    (net (code "104") (name "VCC+3V3_5") (class "Default")
      (node (ref "C101") (pin "2") (pinfunction "2_2") (pintype "passive"))
      (node (ref "U89") (pin "5") (pinfunction "OUT_5") (pintype "passive"))
    )
    (net (code "105") (name "VCC+3V3_6") (class "Default")
      (node (ref "C102") (pin "2") (pinfunction "2_2") (pintype "passive"))
      (node (ref "U90") (pin "5") (pinfunction "OUT_5") (pintype "passive"))
    )
    (net (code "106") (name "VCC+3V3_7") (class "Default")
      (node (ref "C103") (pin "2") (pinfunction "2_2") (pintype "passive"))
      (node (ref "U91") (pin "5") (pinfunction "OUT_5") (pintype "passive"))
    )
    (net (code "107") (name "VCC+5V0-0") (class "Default")
      (node (ref "C25") (pin "2") (pinfunction "2_2") (pintype "passive"))
      (node (ref "C40") (pin "2") (pinfunction "2_2") (pintype "passive"))
      (node (ref "C56") (pin "2") (pinfunction "2_2") (pintype "passive"))
      (node (ref "C72") (pin "2") (pinfunction "2_2") (pintype "passive"))
      (node (ref "C88") (pin "2") (pinfunction "2_2") (pintype "passive"))
      (node (ref "U52") (pin "2") (pinfunction "VOUT_2") (pintype "passive"))
      (node (ref "U60") (pin "1") (pinfunction "IN_1") (pintype "passive"))
      (node (ref "U68") (pin "1") (pinfunction "IN_1") (pintype "passive"))
      (node (ref "U76") (pin "1") (pinfunction "IN_1") (pintype "passive"))
      (node (ref "U84") (pin "1") (pinfunction "IN_1") (pintype "passive"))
    )
    (net (code "108") (name "VCC+5V0-1") (class "Default")
      (node (ref "C27") (pin "2") (pinfunction "2_2") (pintype "passive"))
      (node (ref "C41") (pin "2") (pinfunction "2_2") (pintype "passive"))
      (node (ref "C57") (pin "2") (pinfunction "2_2") (pintype "passive"))
      (node (ref "C73") (pin "2") (pinfunction "2_2") (pintype "passive"))
      (node (ref "C89") (pin "2") (pinfunction "2_2") (pintype "passive"))
      (node (ref "U53") (pin "2") (pinfunction "VOUT_2") (pintype "passive"))
      (node (ref "U61") (pin "1") (pinfunction "IN_1") (pintype "passive"))
      (node (ref "U69") (pin "1") (pinfunction "IN_1") (pintype "passive"))
      (node (ref "U77") (pin "1") (pinfunction "IN_1") (pintype "passive"))
      (node (ref "U85") (pin "1") (pinfunction "IN_1") (pintype "passive"))
    )
    (net (code "109") (name "VCC+5V0-2") (class "Default")
      (node (ref "C29") (pin "2") (pinfunction "2_2") (pintype "passive"))
      (node (ref "C42") (pin "2") (pinfunction "2_2") (pintype "passive"))
      (node (ref "C58") (pin "2") (pinfunction "2_2") (pintype "passive"))
      (node (ref "C74") (pin "2") (pinfunction "2_2") (pintype "passive"))
      (node (ref "C90") (pin "2") (pinfunction "2_2") (pintype "passive"))
      (node (ref "U54") (pin "2") (pinfunction "VOUT_2") (pintype "passive"))
      (node (ref "U62") (pin "1") (pinfunction "IN_1") (pintype "passive"))
      (node (ref "U70") (pin "1") (pinfunction "IN_1") (pintype "passive"))
      (node (ref "U78") (pin "1") (pinfunction "IN_1") (pintype "passive"))
      (node (ref "U86") (pin "1") (pinfunction "IN_1") (pintype "passive"))
    )
    (net (code "110") (name "VCC+5V0-3") (class "Default")
      (node (ref "C31") (pin "2") (pinfunction "2_2") (pintype "passive"))
      (node (ref "C43") (pin "2") (pinfunction "2_2") (pintype "passive"))
      (node (ref "C59") (pin "2") (pinfunction "2_2") (pintype "passive"))
      (node (ref "C75") (pin "2") (pinfunction "2_2") (pintype "passive"))
      (node (ref "C91") (pin "2") (pinfunction "2_2") (pintype "passive"))
      (node (ref "U55") (pin "2") (pinfunction "VOUT_2") (pintype "passive"))
      (node (ref "U63") (pin "1") (pinfunction "IN_1") (pintype "passive"))
      (node (ref "U71") (pin "1") (pinfunction "IN_1") (pintype "passive"))
      (node (ref "U79") (pin "1") (pinfunction "IN_1") (pintype "passive"))
      (node (ref "U87") (pin "1") (pinfunction "IN_1") (pintype "passive"))
    )
    (net (code "111") (name "VCC+5V0-4") (class "Default")
      (node (ref "C33") (pin "2") (pinfunction "2_2") (pintype "passive"))
      (node (ref "C44") (pin "2") (pinfunction "2_2") (pintype "passive"))
      (node (ref "C60") (pin "2") (pinfunction "2_2") (pintype "passive"))
      (node (ref "C76") (pin "2") (pinfunction "2_2") (pintype "passive"))
      (node (ref "C92") (pin "2") (pinfunction "2_2") (pintype "passive"))
      (node (ref "U56") (pin "2") (pinfunction "VOUT_2") (pintype "passive"))
      (node (ref "U64") (pin "1") (pinfunction "IN_1") (pintype "passive"))
      (node (ref "U72") (pin "1") (pinfunction "IN_1") (pintype "passive"))
      (node (ref "U80") (pin "1") (pinfunction "IN_1") (pintype "passive"))
      (node (ref "U88") (pin "1") (pinfunction "IN_1") (pintype "passive"))
    )
    (net (code "112") (name "VCC+5V0-5") (class "Default")
      (node (ref "C35") (pin "2") (pinfunction "2_2") (pintype "passive"))
      (node (ref "C45") (pin "2") (pinfunction "2_2") (pintype "passive"))
      (node (ref "C61") (pin "2") (pinfunction "2_2") (pintype "passive"))
      (node (ref "C77") (pin "2") (pinfunction "2_2") (pintype "passive"))
      (node (ref "C93") (pin "2") (pinfunction "2_2") (pintype "passive"))
      (node (ref "U57") (pin "2") (pinfunction "VOUT_2") (pintype "passive"))
      (node (ref "U65") (pin "1") (pinfunction "IN_1") (pintype "passive"))
      (node (ref "U73") (pin "1") (pinfunction "IN_1") (pintype "passive"))
      (node (ref "U81") (pin "1") (pinfunction "IN_1") (pintype "passive"))
      (node (ref "U89") (pin "1") (pinfunction "IN_1") (pintype "passive"))
    )
    (net (code "113") (name "VCC+5V0-6") (class "Default")
      (node (ref "C37") (pin "2") (pinfunction "2_2") (pintype "passive"))
      (node (ref "C46") (pin "2") (pinfunction "2_2") (pintype "passive"))
      (node (ref "C62") (pin "2") (pinfunction "2_2") (pintype "passive"))
      (node (ref "C78") (pin "2") (pinfunction "2_2") (pintype "passive"))
      (node (ref "C94") (pin "2") (pinfunction "2_2") (pintype "passive"))
      (node (ref "U58") (pin "2") (pinfunction "VOUT_2") (pintype "passive"))
      (node (ref "U66") (pin "1") (pinfunction "IN_1") (pintype "passive"))
      (node (ref "U74") (pin "1") (pinfunction "IN_1") (pintype "passive"))
      (node (ref "U82") (pin "1") (pinfunction "IN_1") (pintype "passive"))
      (node (ref "U90") (pin "1") (pinfunction "IN_1") (pintype "passive"))
    )
    (net (code "114") (name "VCC+5V0-7") (class "Default")
      (node (ref "C39") (pin "2") (pinfunction "2_2") (pintype "passive"))
      (node (ref "C47") (pin "2") (pinfunction "2_2") (pintype "passive"))
      (node (ref "C63") (pin "2") (pinfunction "2_2") (pintype "passive"))
      (node (ref "C79") (pin "2") (pinfunction "2_2") (pintype "passive"))
      (node (ref "C95") (pin "2") (pinfunction "2_2") (pintype "passive"))
      (node (ref "U59") (pin "2") (pinfunction "VOUT_2") (pintype "passive"))
      (node (ref "U67") (pin "1") (pinfunction "IN_1") (pintype "passive"))
      (node (ref "U75") (pin "1") (pinfunction "IN_1") (pintype "passive"))
      (node (ref "U83") (pin "1") (pinfunction "IN_1") (pintype "passive"))
      (node (ref "U91") (pin "1") (pinfunction "IN_1") (pintype "passive"))
    )
    (net (code "115") (name "VCC+12V0") (class "Default")
      (node (ref "C104") (pin "2") (pinfunction "2_2") (pintype "passive"))
      (node (ref "C106") (pin "2") (pinfunction "2_2") (pintype "passive"))
      (node (ref "C108") (pin "2") (pinfunction "2_2") (pintype "passive"))
      (node (ref "C110") (pin "2") (pinfunction "2_2") (pintype "passive"))
      (node (ref "C112") (pin "2") (pinfunction "2_2") (pintype "passive"))
      (node (ref "C114") (pin "2") (pinfunction "2_2") (pintype "passive"))
      (node (ref "C116") (pin "2") (pinfunction "2_2") (pintype "passive"))
      (node (ref "C118") (pin "2") (pinfunction "2_2") (pintype "passive"))
      (node (ref "C24") (pin "2") (pinfunction "2_2") (pintype "passive"))
      (node (ref "C26") (pin "2") (pinfunction "2_2") (pintype "passive"))
      (node (ref "C28") (pin "2") (pinfunction "2_2") (pintype "passive"))
      (node (ref "C30") (pin "2") (pinfunction "2_2") (pintype "passive"))
      (node (ref "C32") (pin "2") (pinfunction "2_2") (pintype "passive"))
      (node (ref "C34") (pin "2") (pinfunction "2_2") (pintype "passive"))
      (node (ref "C36") (pin "2") (pinfunction "2_2") (pintype "passive"))
      (node (ref "C38") (pin "2") (pinfunction "2_2") (pintype "passive"))
      (node (ref "U100") (pin "8") (pinfunction "V+_8") (pintype "passive"))
      (node (ref "U101") (pin "8") (pinfunction "V+_8") (pintype "passive"))
      (node (ref "U102") (pin "8") (pinfunction "V+_8") (pintype "passive"))
      (node (ref "U103") (pin "8") (pinfunction "V+_8") (pintype "passive"))
      (node (ref "U104") (pin "5") (pinfunction "VSS_5") (pintype "passive"))
      (node (ref "U105") (pin "5") (pinfunction "VSS_5") (pintype "passive"))
      (node (ref "U106") (pin "5") (pinfunction "VSS_5") (pintype "passive"))
      (node (ref "U107") (pin "5") (pinfunction "VSS_5") (pintype "passive"))
      (node (ref "U108") (pin "5") (pinfunction "VSS_5") (pintype "passive"))
      (node (ref "U109") (pin "5") (pinfunction "VSS_5") (pintype "passive"))
      (node (ref "U110") (pin "5") (pinfunction "VSS_5") (pintype "passive"))
      (node (ref "U111") (pin "5") (pinfunction "VSS_5") (pintype "passive"))
      (node (ref "U112") (pin "5") (pinfunction "VSS_5") (pintype "passive"))
      (node (ref "U113") (pin "5") (pinfunction "VSS_5") (pintype "passive"))
      (node (ref "U114") (pin "5") (pinfunction "VSS_5") (pintype "passive"))
      (node (ref "U115") (pin "5") (pinfunction "VSS_5") (pintype "passive"))
      (node (ref "U116") (pin "5") (pinfunction "VSS_5") (pintype "passive"))
      (node (ref "U117") (pin "5") (pinfunction "VSS_5") (pintype "passive"))
      (node (ref "U118") (pin "5") (pinfunction "VSS_5") (pintype "passive"))
      (node (ref "U119") (pin "5") (pinfunction "VSS_5") (pintype "passive"))
      (node (ref "U52") (pin "3") (pinfunction "VIN_3") (pintype "passive"))
      (node (ref "U53") (pin "3") (pinfunction "VIN_3") (pintype "passive"))
      (node (ref "U54") (pin "3") (pinfunction "VIN_3") (pintype "passive"))
      (node (ref "U55") (pin "3") (pinfunction "VIN_3") (pintype "passive"))
      (node (ref "U56") (pin "3") (pinfunction "VIN_3") (pintype "passive"))
      (node (ref "U57") (pin "3") (pinfunction "VIN_3") (pintype "passive"))
      (node (ref "U58") (pin "3") (pinfunction "VIN_3") (pintype "passive"))
      (node (ref "U59") (pin "3") (pinfunction "VIN_3") (pintype "passive"))
      (node (ref "U92") (pin "3") (pinfunction "IN_3") (pintype "passive"))
      (node (ref "U93") (pin "3") (pinfunction "IN_3") (pintype "passive"))
      (node (ref "U94") (pin "3") (pinfunction "IN_3") (pintype "passive"))
      (node (ref "U95") (pin "3") (pinfunction "IN_3") (pintype "passive"))
      (node (ref "U96") (pin "3") (pinfunction "IN_3") (pintype "passive"))
      (node (ref "U97") (pin "3") (pinfunction "IN_3") (pintype "passive"))
      (node (ref "U98") (pin "3") (pinfunction "IN_3") (pintype "passive"))
      (node (ref "U99") (pin "3") (pinfunction "IN_3") (pintype "passive"))
    )
    (net (code "116") (name "VCC+ADJ_0") (class "Default")
      (node (ref "R242") (pin "2") (pinfunction "2_2") (pintype "passive"))
      (node (ref "U104") (pin "4") (pinfunction "IN-_4") (pintype "passive"))
      (node (ref "U112") (pin "4") (pinfunction "IN-_4") (pintype "passive"))
    )
    (net (code "117") (name "VCC+ADJ_1") (class "Default")
      (node (ref "R243") (pin "2") (pinfunction "2_2") (pintype "passive"))
      (node (ref "U105") (pin "4") (pinfunction "IN-_4") (pintype "passive"))
      (node (ref "U113") (pin "4") (pinfunction "IN-_4") (pintype "passive"))
    )
    (net (code "118") (name "VCC+ADJ_2") (class "Default")
      (node (ref "R244") (pin "2") (pinfunction "2_2") (pintype "passive"))
      (node (ref "U106") (pin "4") (pinfunction "IN-_4") (pintype "passive"))
      (node (ref "U114") (pin "4") (pinfunction "IN-_4") (pintype "passive"))
    )
    (net (code "119") (name "VCC+ADJ_3") (class "Default")
      (node (ref "R245") (pin "2") (pinfunction "2_2") (pintype "passive"))
      (node (ref "U107") (pin "4") (pinfunction "IN-_4") (pintype "passive"))
      (node (ref "U115") (pin "4") (pinfunction "IN-_4") (pintype "passive"))
    )
    (net (code "120") (name "VCC+ADJ_4") (class "Default")
      (node (ref "R246") (pin "2") (pinfunction "2_2") (pintype "passive"))
      (node (ref "U108") (pin "4") (pinfunction "IN-_4") (pintype "passive"))
      (node (ref "U116") (pin "4") (pinfunction "IN-_4") (pintype "passive"))
    )
    (net (code "121") (name "VCC+ADJ_5") (class "Default")
      (node (ref "R247") (pin "2") (pinfunction "2_2") (pintype "passive"))
      (node (ref "U109") (pin "4") (pinfunction "IN-_4") (pintype "passive"))
      (node (ref "U117") (pin "4") (pinfunction "IN-_4") (pintype "passive"))
    )
    (net (code "122") (name "VCC+ADJ_6") (class "Default")
      (node (ref "R248") (pin "2") (pinfunction "2_2") (pintype "passive"))
      (node (ref "U110") (pin "4") (pinfunction "IN-_4") (pintype "passive"))
      (node (ref "U118") (pin "4") (pinfunction "IN-_4") (pintype "passive"))
    )
    (net (code "123") (name "VCC+ADJ_7") (class "Default")
      (node (ref "R249") (pin "2") (pinfunction "2_2") (pintype "passive"))
      (node (ref "U111") (pin "4") (pinfunction "IN-_4") (pintype "passive"))
      (node (ref "U119") (pin "4") (pinfunction "IN-_4") (pintype "passive"))
    )
    (net (code "124") (name "unconnected-(U60-NC-Pad4)") (class "Default")
      (node (ref "U60") (pin "4") (pinfunction "NC_4") (pintype "passive+no_connect"))
    )
    (net (code "125") (name "unconnected-(U61-NC-Pad4)") (class "Default")
      (node (ref "U61") (pin "4") (pinfunction "NC_4") (pintype "passive+no_connect"))
    )
    (net (code "126") (name "unconnected-(U62-NC-Pad4)") (class "Default")
      (node (ref "U62") (pin "4") (pinfunction "NC_4") (pintype "passive+no_connect"))
    )
    (net (code "127") (name "unconnected-(U63-NC-Pad4)") (class "Default")
      (node (ref "U63") (pin "4") (pinfunction "NC_4") (pintype "passive+no_connect"))
    )
    (net (code "128") (name "unconnected-(U64-NC-Pad4)") (class "Default")
      (node (ref "U64") (pin "4") (pinfunction "NC_4") (pintype "passive+no_connect"))
    )
    (net (code "129") (name "unconnected-(U65-NC-Pad4)") (class "Default")
      (node (ref "U65") (pin "4") (pinfunction "NC_4") (pintype "passive+no_connect"))
    )
    (net (code "130") (name "unconnected-(U66-NC-Pad4)") (class "Default")
      (node (ref "U66") (pin "4") (pinfunction "NC_4") (pintype "passive+no_connect"))
    )
    (net (code "131") (name "unconnected-(U67-NC-Pad4)") (class "Default")
      (node (ref "U67") (pin "4") (pinfunction "NC_4") (pintype "passive+no_connect"))
    )
    (net (code "132") (name "unconnected-(U68-NC-Pad4)") (class "Default")
      (node (ref "U68") (pin "4") (pinfunction "NC_4") (pintype "passive+no_connect"))
    )
    (net (code "133") (name "unconnected-(U69-NC-Pad4)") (class "Default")
      (node (ref "U69") (pin "4") (pinfunction "NC_4") (pintype "passive+no_connect"))
    )
    (net (code "134") (name "unconnected-(U70-NC-Pad4)") (class "Default")
      (node (ref "U70") (pin "4") (pinfunction "NC_4") (pintype "passive+no_connect"))
    )
    (net (code "135") (name "unconnected-(U71-NC-Pad4)") (class "Default")
      (node (ref "U71") (pin "4") (pinfunction "NC_4") (pintype "passive+no_connect"))
    )
    (net (code "136") (name "unconnected-(U72-NC-Pad4)") (class "Default")
      (node (ref "U72") (pin "4") (pinfunction "NC_4") (pintype "passive+no_connect"))
    )
    (net (code "137") (name "unconnected-(U73-NC-Pad4)") (class "Default")
      (node (ref "U73") (pin "4") (pinfunction "NC_4") (pintype "passive+no_connect"))
    )
    (net (code "138") (name "unconnected-(U74-NC-Pad4)") (class "Default")
      (node (ref "U74") (pin "4") (pinfunction "NC_4") (pintype "passive+no_connect"))
    )
    (net (code "139") (name "unconnected-(U75-NC-Pad4)") (class "Default")
      (node (ref "U75") (pin "4") (pinfunction "NC_4") (pintype "passive+no_connect"))
    )
    (net (code "140") (name "unconnected-(U76-NC-Pad4)") (class "Default")
      (node (ref "U76") (pin "4") (pinfunction "NC_4") (pintype "passive+no_connect"))
    )
    (net (code "141") (name "unconnected-(U77-NC-Pad4)") (class "Default")
      (node (ref "U77") (pin "4") (pinfunction "NC_4") (pintype "passive+no_connect"))
    )
    (net (code "142") (name "unconnected-(U78-NC-Pad4)") (class "Default")
      (node (ref "U78") (pin "4") (pinfunction "NC_4") (pintype "passive+no_connect"))
    )
    (net (code "143") (name "unconnected-(U79-NC-Pad4)") (class "Default")
      (node (ref "U79") (pin "4") (pinfunction "NC_4") (pintype "passive+no_connect"))
    )
    (net (code "144") (name "unconnected-(U80-NC-Pad4)") (class "Default")
      (node (ref "U80") (pin "4") (pinfunction "NC_4") (pintype "passive+no_connect"))
    )
    (net (code "145") (name "unconnected-(U81-NC-Pad4)") (class "Default")
      (node (ref "U81") (pin "4") (pinfunction "NC_4") (pintype "passive+no_connect"))
    )
    (net (code "146") (name "unconnected-(U82-NC-Pad4)") (class "Default")
      (node (ref "U82") (pin "4") (pinfunction "NC_4") (pintype "passive+no_connect"))
    )
    (net (code "147") (name "unconnected-(U83-NC-Pad4)") (class "Default")
      (node (ref "U83") (pin "4") (pinfunction "NC_4") (pintype "passive+no_connect"))
    )
    (net (code "148") (name "unconnected-(U84-NC-Pad4)") (class "Default")
      (node (ref "U84") (pin "4") (pinfunction "NC_4") (pintype "passive+no_connect"))
    )
    (net (code "149") (name "unconnected-(U85-NC-Pad4)") (class "Default")
      (node (ref "U85") (pin "4") (pinfunction "NC_4") (pintype "passive+no_connect"))
    )
    (net (code "150") (name "unconnected-(U86-NC-Pad4)") (class "Default")
      (node (ref "U86") (pin "4") (pinfunction "NC_4") (pintype "passive+no_connect"))
    )
    (net (code "151") (name "unconnected-(U87-NC-Pad4)") (class "Default")
      (node (ref "U87") (pin "4") (pinfunction "NC_4") (pintype "passive+no_connect"))
    )
    (net (code "152") (name "unconnected-(U88-NC-Pad4)") (class "Default")
      (node (ref "U88") (pin "4") (pinfunction "NC_4") (pintype "passive+no_connect"))
    )
    (net (code "153") (name "unconnected-(U89-NC-Pad4)") (class "Default")
      (node (ref "U89") (pin "4") (pinfunction "NC_4") (pintype "passive+no_connect"))
    )
    (net (code "154") (name "unconnected-(U90-NC-Pad4)") (class "Default")
      (node (ref "U90") (pin "4") (pinfunction "NC_4") (pintype "passive+no_connect"))
    )
    (net (code "155") (name "unconnected-(U91-NC-Pad4)") (class "Default")
      (node (ref "U91") (pin "4") (pinfunction "NC_4") (pintype "passive+no_connect"))
    )
  )
)
